# Misaka-v1_0.net
KiCad netlist of a schematic drawn in Altium Designer
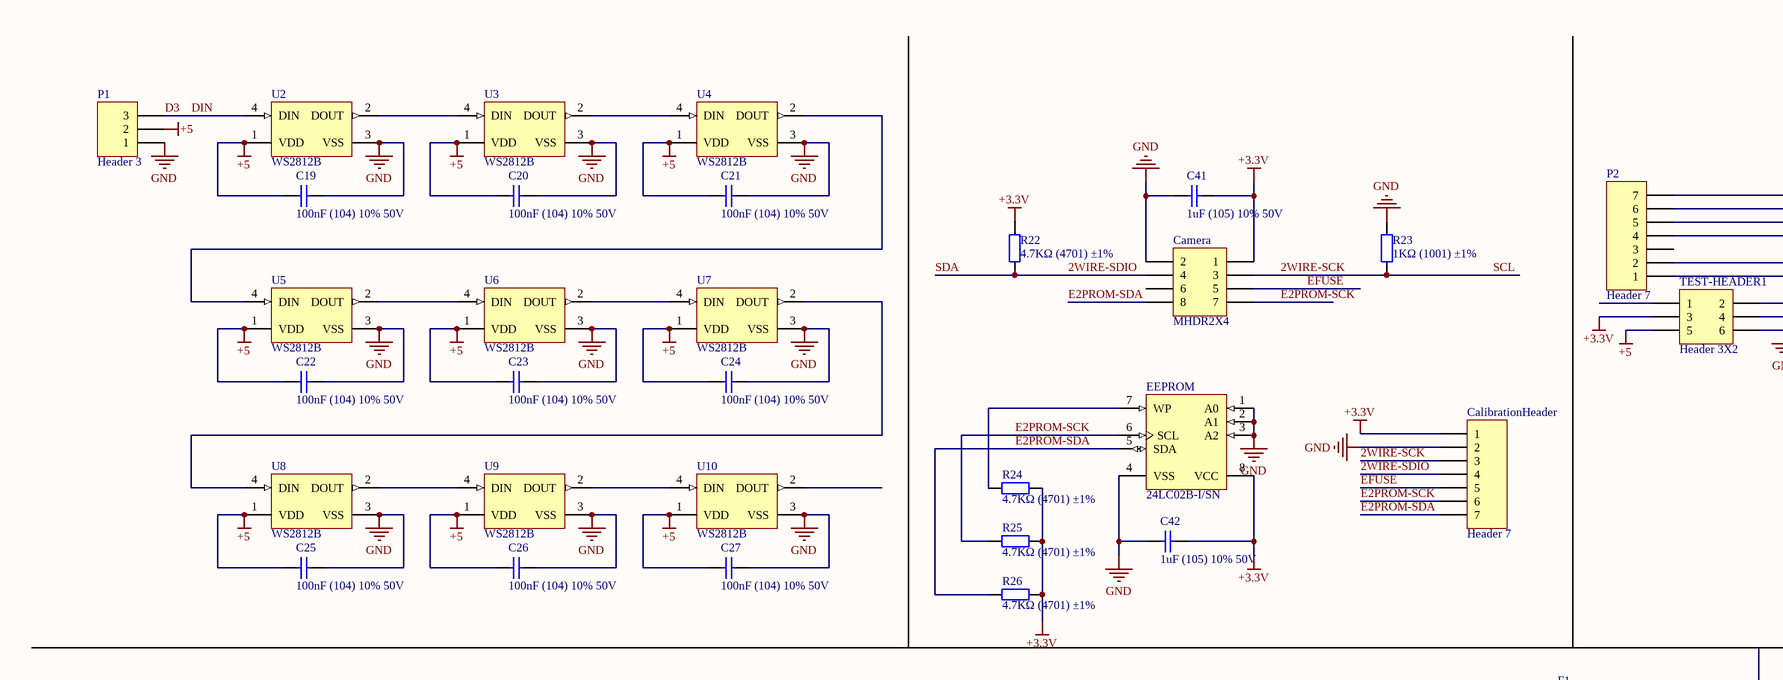
[diagram p0: Misaka-v1.0.SchDoc, top left]
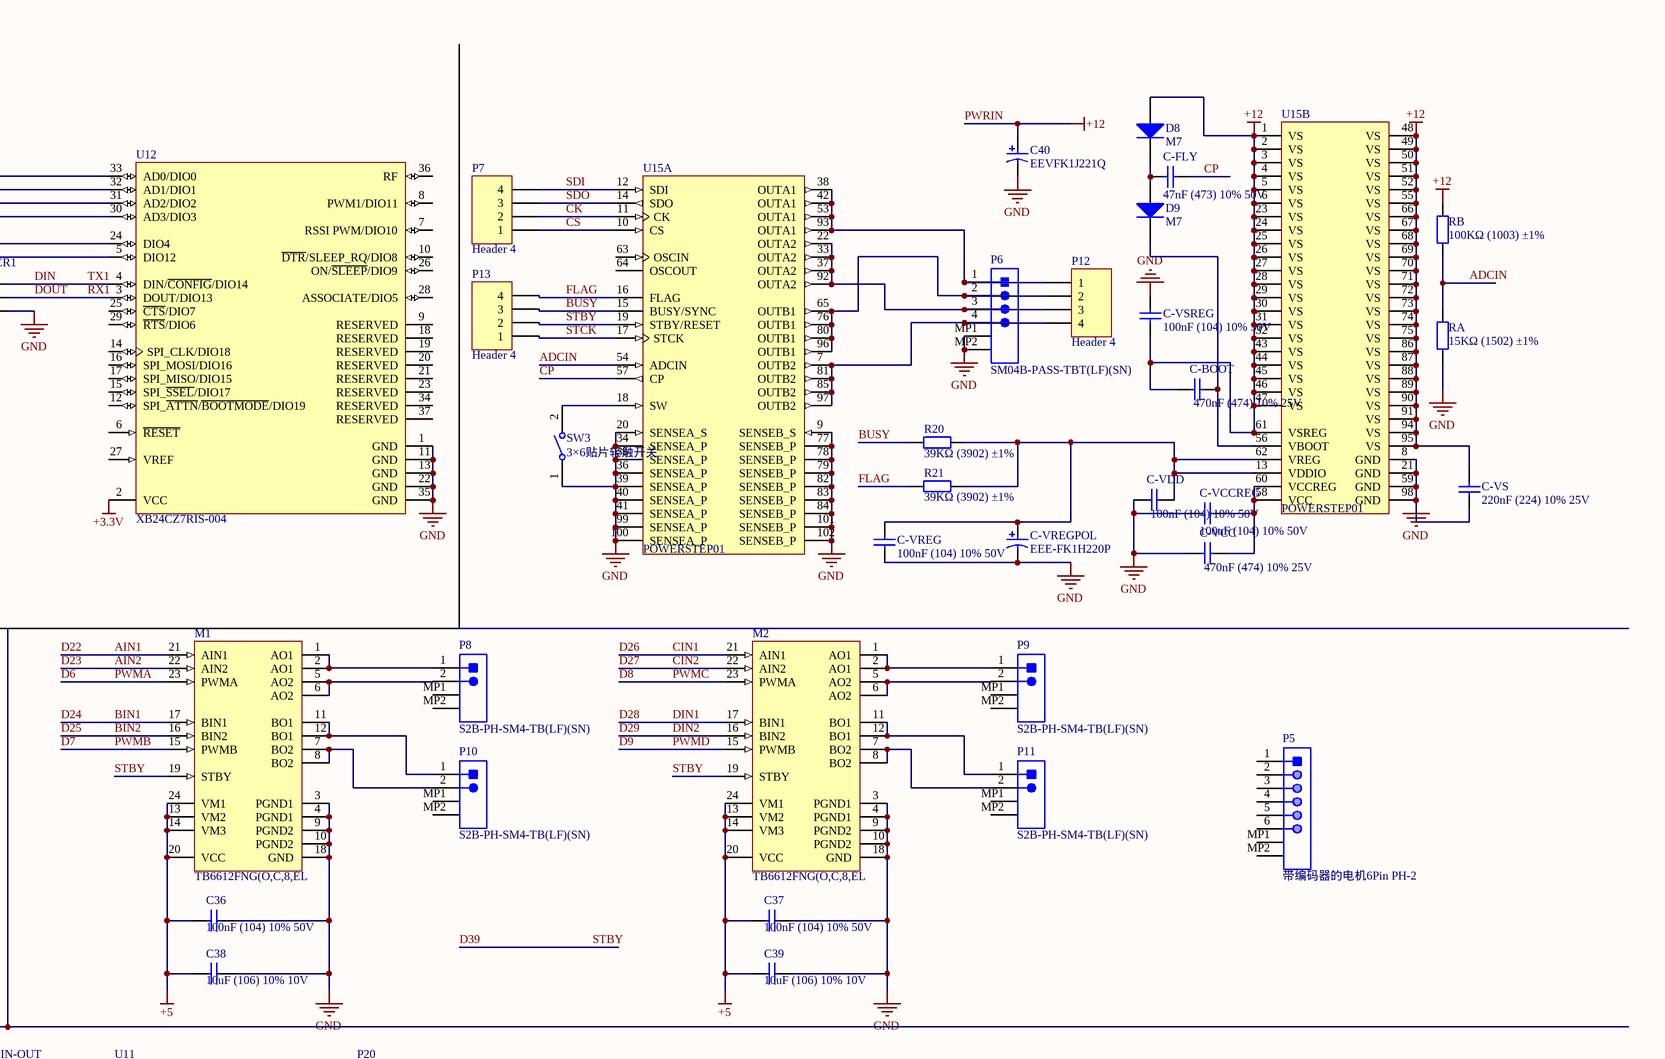
[diagram p1: Misaka-v1.0.SchDoc, top right]
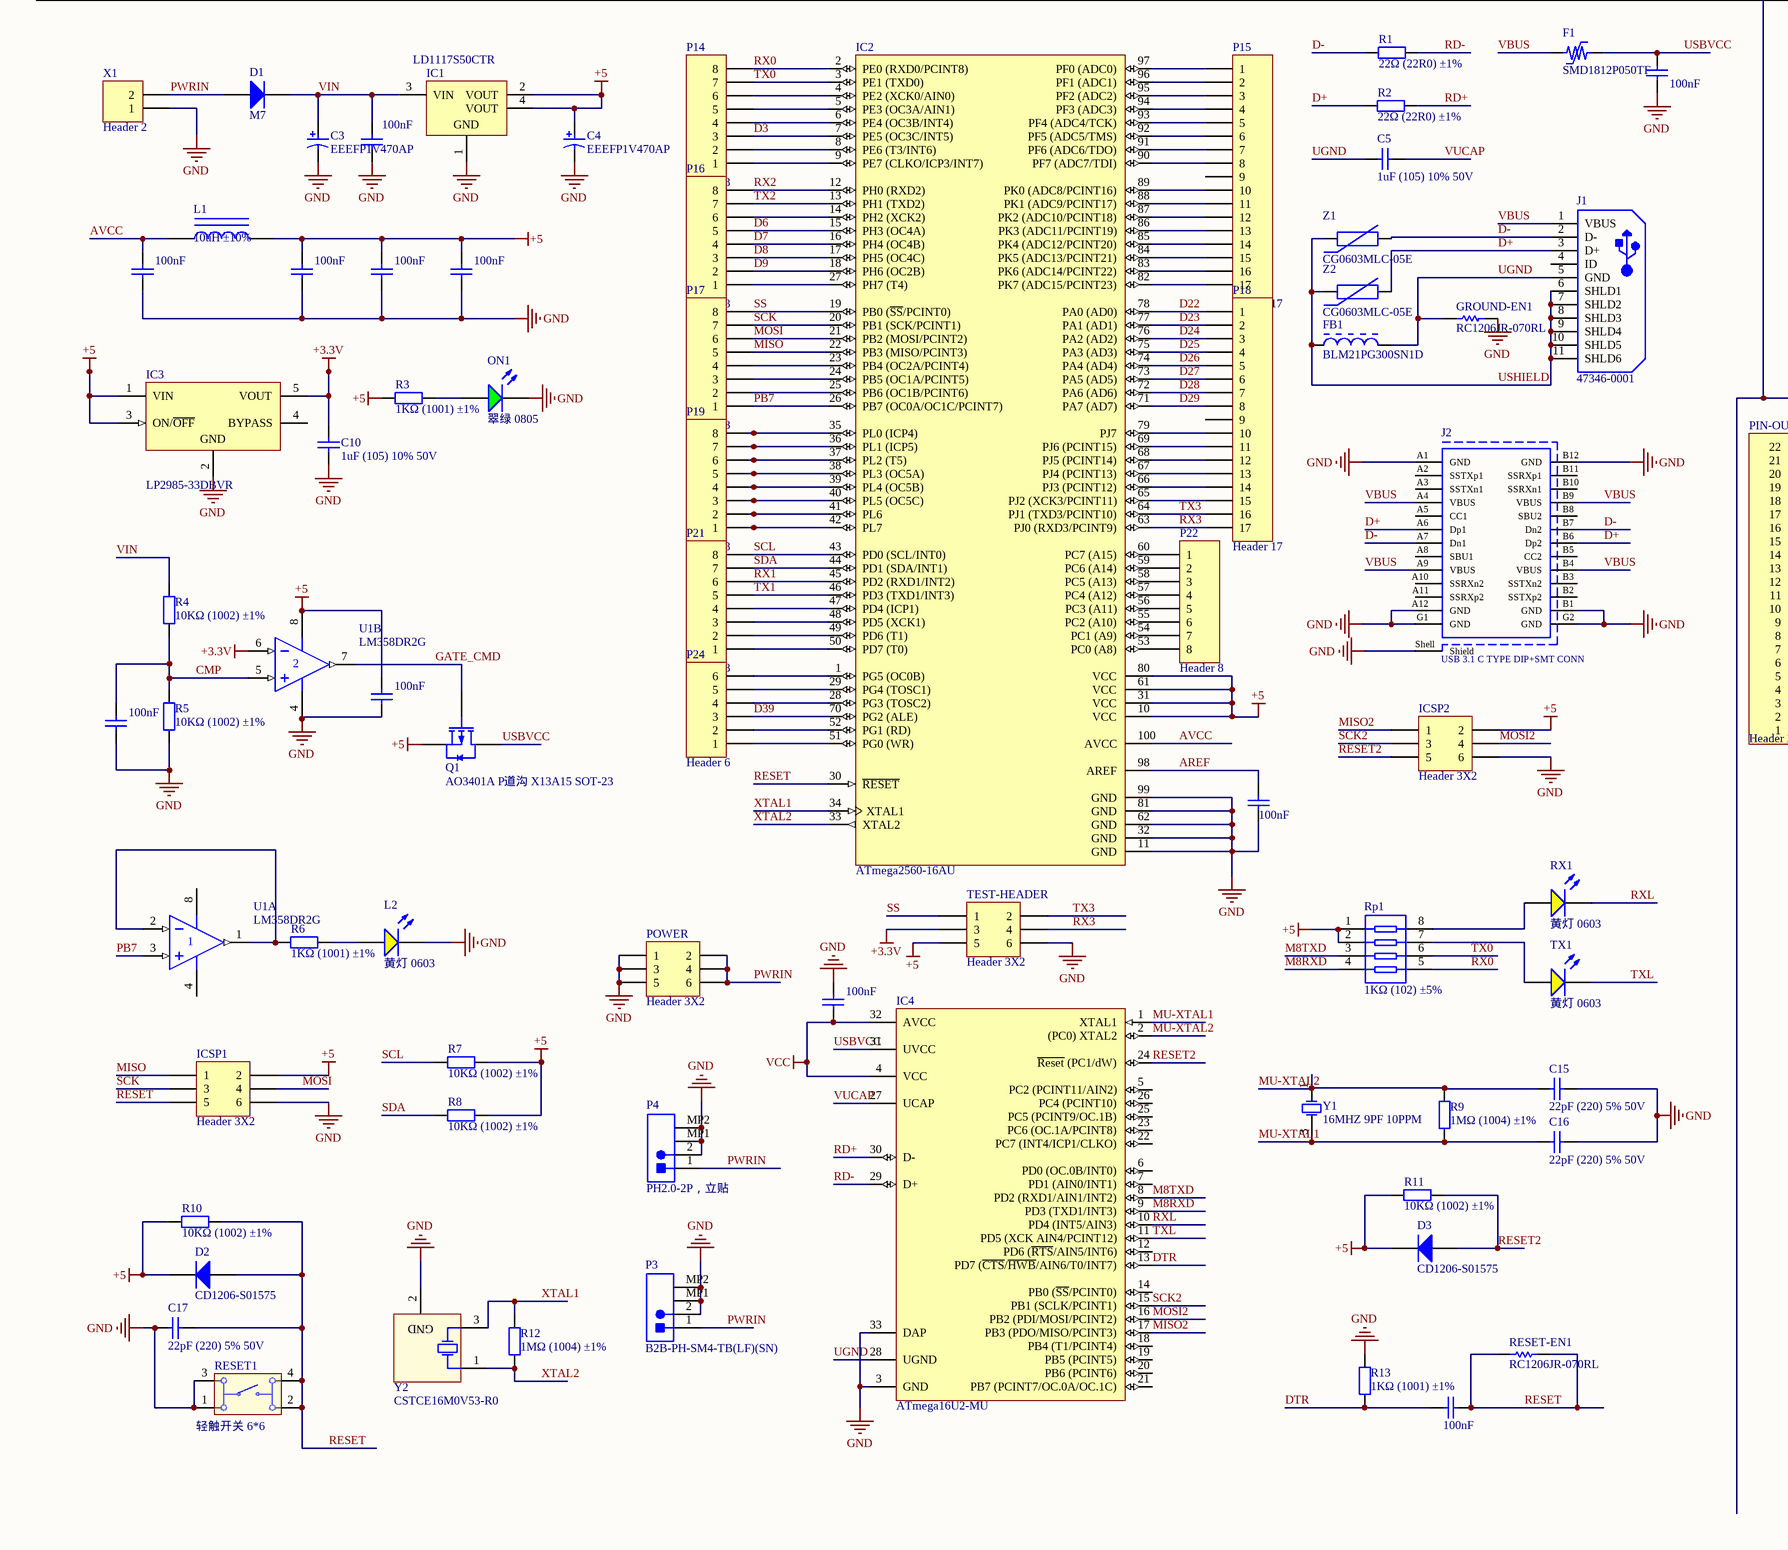
[diagram p2: Misaka-v1.0.SchDoc, bottom left]
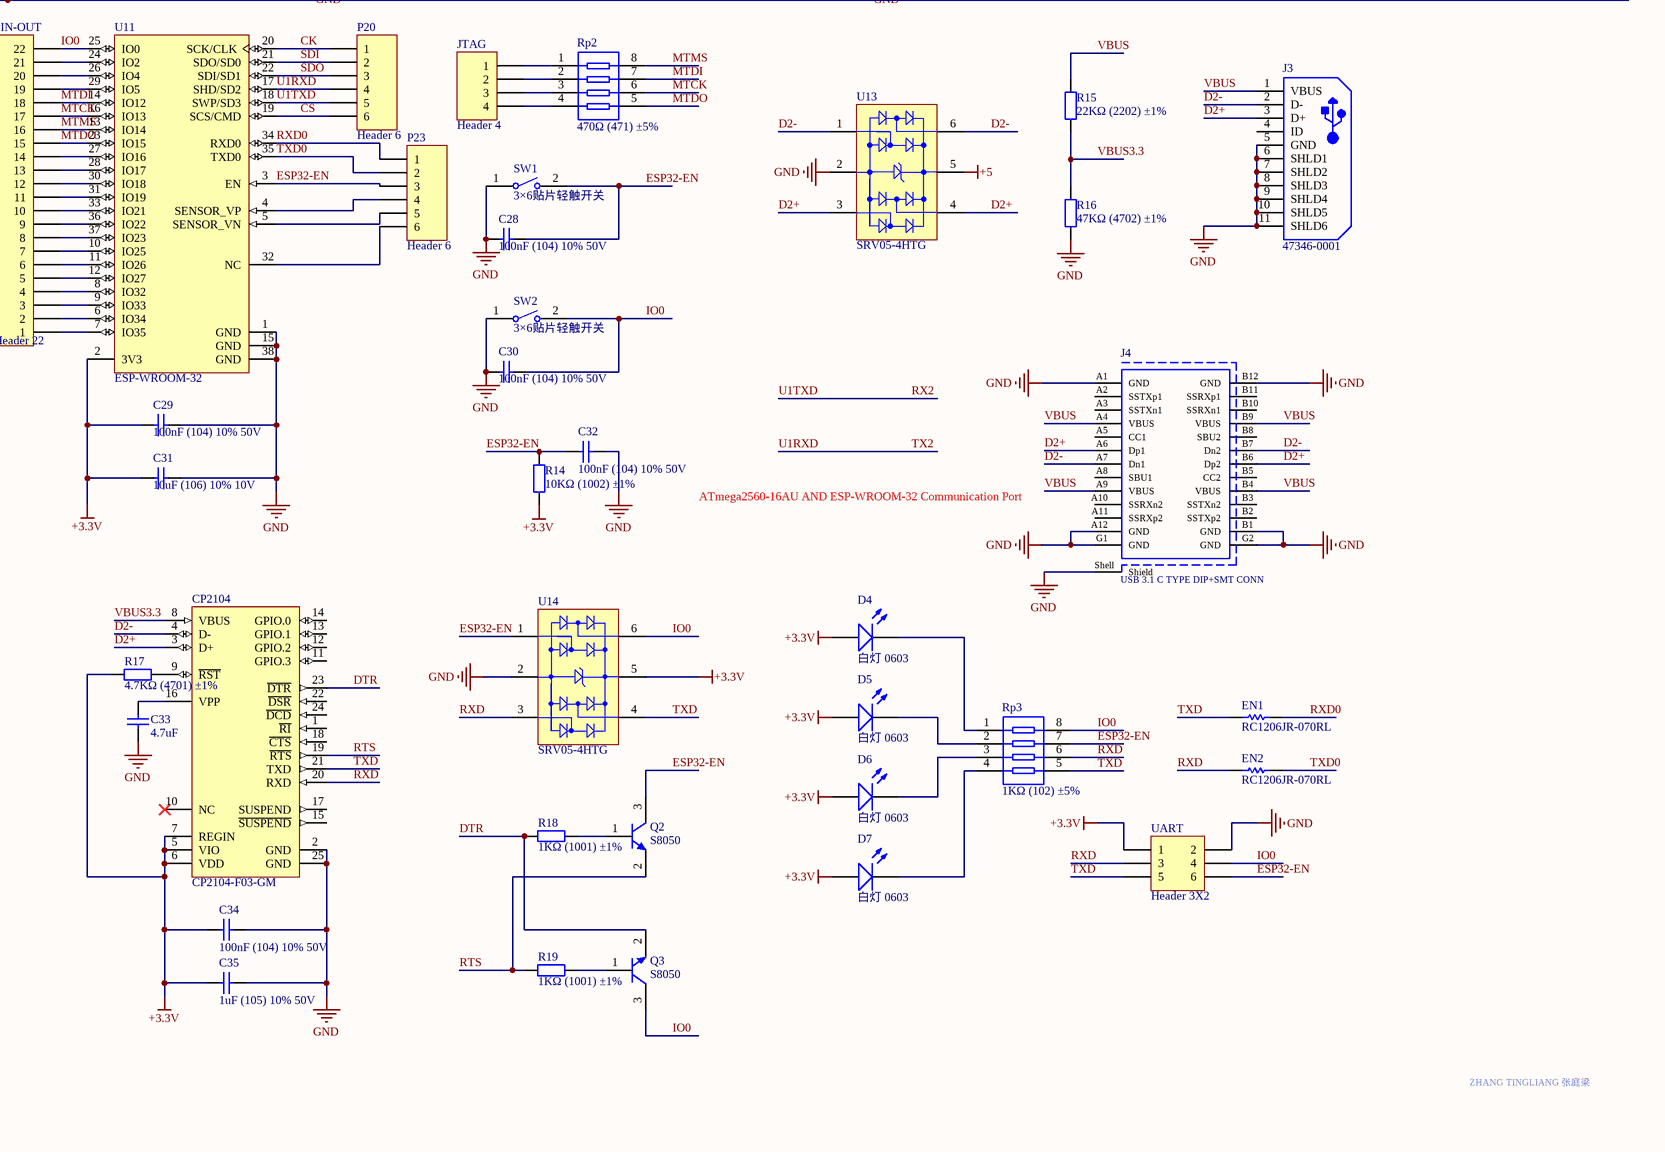
[diagram p3: Misaka-v1.0.SchDoc, bottom right]

(export (version "E")
  (design (tool "Eeschema 10.0.6"))
  (components
    (comp (ref "C-BOOT")
      (value "470nF (474) 10% 25V")
      (footprint "0603_C")
      (description "贴片电容")
      (libsource (lib "Miscellaneous Devices LC") (part "0603 470nF (474) 10% 25V"))
    )
    (comp (ref "C-FLY")
      (value "47nF (473) 10% 50V")
      (footprint "0603_C")
      (description "贴片电容")
      (libsource (lib "Miscellaneous Devices LC") (part "0603 47nF (473) 10% 50V"))
    )
    (comp (ref "C-VCC")
      (value "470nF (474) 10% 25V")
      (footprint "0603_C")
      (description "贴片电容")
      (libsource (lib "Miscellaneous Devices LC") (part "0603 470nF (474) 10% 25V"))
    )
    (comp (ref "C-VCCREG")
      (value "100nF (104) 10% 50V")
      (footprint "0603_C")
      (description "贴片电容")
      (libsource (lib "Miscellaneous Devices LC") (part "0603 100nF (104) 10% 50V"))
    )
    (comp (ref "C-VDD")
      (value "100nF (104) 10% 50V")
      (footprint "0603_C")
      (description "贴片电容")
      (libsource (lib "Miscellaneous Devices LC") (part "0603 100nF (104) 10% 50V"))
    )
    (comp (ref "C-VREG")
      (value "100nF (104) 10% 50V")
      (footprint "0603_C")
      (description "贴片电容")
      (libsource (lib "Miscellaneous Devices LC") (part "0603 100nF (104) 10% 50V"))
    )
    (comp (ref "C-VREGPOL")
      (value "EEE-FK1H220P")
      (footprint "PNSC-EEE-FK1H220P_L")
      (description "Cap Aluminum Lytic, 22 uF, +/- 20%, 6.3 to 100 V, -55 to 105 degC, 2-Pin SMD, RoHS, Tape and Reel")
      (fields (field (name "MANUFACTURER") "Panasonic"))
      (libsource (lib "Altium Content Vault") (part "CAP-P-2"))
    )
    (comp (ref "C-VS")
      (value "220nF (224) 10% 25V")
      (footprint "0603_C")
      (description "贴片电容")
      (libsource (lib "Miscellaneous Devices LC") (part "0603 220nF (224) 10% 25V"))
    )
    (comp (ref "C-VSREG")
      (value "100nF (104) 10% 50V")
      (footprint "0603_C")
      (description "贴片电容")
      (libsource (lib "Miscellaneous Devices LC") (part "0603 100nF (104) 10% 50V"))
    )
    (comp (ref "C1")
      (value "100nF")
      (footprint "0603_C")
      (description "贴片电容")
      (libsource (lib "Miscellaneous Devices LC") (part "0603 100nF (104) 10% 50V"))
    )
    (comp (ref "C2")
      (value "100nF")
      (footprint "0603_C")
      (description "贴片电容")
      (libsource (lib "Miscellaneous Devices LC") (part "0603 100nF (104) 10% 50V"))
    )
    (comp (ref "C3")
      (value "EEEFP1V470AP")
      (footprint "PNSC-FP-V-D_V")
      (fields (field (name "MANUFACTURER") "Panasonic"))
      (libsource (lib "Altium Content Vault") (part "CAP-P-2"))
    )
    (comp (ref "C4")
      (value "EEEFP1V470AP")
      (footprint "PNSC-FP-V-D_V")
      (fields (field (name "MANUFACTURER") "Panasonic"))
      (libsource (lib "Altium Content Vault") (part "CAP-P-2"))
    )
    (comp (ref "C5")
      (value "1uF (105) 10% 50V")
      (footprint "0603_C")
      (description "贴片电容")
      (libsource (lib "Miscellaneous Devices LC") (part "0603 1uF (105) 10% 50V"))
    )
    (comp (ref "C6")
      (value "100nF")
      (footprint "0603_C")
      (description "贴片电容")
      (libsource (lib "Miscellaneous Devices LC") (part "0603 100nF (104) 10% 50V"))
    )
    (comp (ref "C7")
      (value "100nF")
      (footprint "0603_C")
      (description "贴片电容")
      (libsource (lib "Miscellaneous Devices LC") (part "0603 100nF (104) 10% 50V"))
    )
    (comp (ref "C8")
      (value "100nF")
      (footprint "0603_C")
      (description "贴片电容")
      (libsource (lib "Miscellaneous Devices LC") (part "0603 100nF (104) 10% 50V"))
    )
    (comp (ref "C9")
      (value "100nF")
      (footprint "0603_C")
      (description "贴片电容")
      (libsource (lib "Miscellaneous Devices LC") (part "0603 100nF (104) 10% 50V"))
    )
    (comp (ref "C10")
      (value "1uF (105) 10% 50V")
      (footprint "0603_C")
      (description "贴片电容")
      (libsource (lib "Miscellaneous Devices LC") (part "0603 1uF (105) 10% 50V"))
    )
    (comp (ref "C11")
      (value "100nF")
      (footprint "0603_C")
      (description "贴片电容")
      (libsource (lib "Miscellaneous Devices LC") (part "0603 100nF (104) 10% 50V"))
    )
    (comp (ref "C12")
      (value "100nF")
      (footprint "0603_C")
      (description "贴片电容")
      (libsource (lib "Miscellaneous Devices LC") (part "0603 100nF (104) 10% 50V"))
    )
    (comp (ref "C13")
      (value "100nF")
      (footprint "0603_C")
      (description "贴片电容")
      (libsource (lib "Miscellaneous Devices LC") (part "0603 100nF (104) 10% 50V"))
    )
    (comp (ref "C14")
      (value "100nF")
      (footprint "0603_C")
      (description "贴片电容")
      (libsource (lib "Miscellaneous Devices LC") (part "0603 100nF (104) 10% 50V"))
    )
    (comp (ref "C15")
      (value "22pF (220) 5% 50V")
      (footprint "0603_C")
      (description "贴片电容")
      (libsource (lib "Miscellaneous Devices LC") (part "0603 22pF (220) 5% 50V"))
    )
    (comp (ref "C16")
      (value "22pF (220) 5% 50V")
      (footprint "0603_C")
      (description "贴片电容")
      (libsource (lib "Miscellaneous Devices LC") (part "0603 22pF (220) 5% 50V"))
    )
    (comp (ref "C17")
      (value "22pF (220) 5% 50V")
      (footprint "0603_C")
      (description "贴片电容")
      (libsource (lib "Miscellaneous Devices LC") (part "0603 22pF (220) 5% 50V"))
    )
    (comp (ref "C18")
      (value "100nF")
      (footprint "0603_C")
      (description "贴片电容")
      (libsource (lib "Miscellaneous Devices LC") (part "0603 100nF (104) 10% 50V"))
    )
    (comp (ref "C19")
      (value "100nF (104) 10% 50V")
      (footprint "0603_C")
      (description "贴片电容")
      (libsource (lib "Miscellaneous Devices LC") (part "0603 100nF (104) 10% 50V"))
    )
    (comp (ref "C20")
      (value "100nF (104) 10% 50V")
      (footprint "0603_C")
      (description "贴片电容")
      (libsource (lib "Miscellaneous Devices LC") (part "0603 100nF (104) 10% 50V"))
    )
    (comp (ref "C21")
      (value "100nF (104) 10% 50V")
      (footprint "0603_C")
      (description "贴片电容")
      (libsource (lib "Miscellaneous Devices LC") (part "0603 100nF (104) 10% 50V"))
    )
    (comp (ref "C22")
      (value "100nF (104) 10% 50V")
      (footprint "0603_C")
      (description "贴片电容")
      (libsource (lib "Miscellaneous Devices LC") (part "0603 100nF (104) 10% 50V"))
    )
    (comp (ref "C23")
      (value "100nF (104) 10% 50V")
      (footprint "0603_C")
      (description "贴片电容")
      (libsource (lib "Miscellaneous Devices LC") (part "0603 100nF (104) 10% 50V"))
    )
    (comp (ref "C24")
      (value "100nF (104) 10% 50V")
      (footprint "0603_C")
      (description "贴片电容")
      (libsource (lib "Miscellaneous Devices LC") (part "0603 100nF (104) 10% 50V"))
    )
    (comp (ref "C25")
      (value "100nF (104) 10% 50V")
      (footprint "0603_C")
      (description "贴片电容")
      (libsource (lib "Miscellaneous Devices LC") (part "0603 100nF (104) 10% 50V"))
    )
    (comp (ref "C26")
      (value "100nF (104) 10% 50V")
      (footprint "0603_C")
      (description "贴片电容")
      (libsource (lib "Miscellaneous Devices LC") (part "0603 100nF (104) 10% 50V"))
    )
    (comp (ref "C27")
      (value "100nF (104) 10% 50V")
      (footprint "0603_C")
      (description "贴片电容")
      (libsource (lib "Miscellaneous Devices LC") (part "0603 100nF (104) 10% 50V"))
    )
    (comp (ref "C28")
      (value "100nF (104) 10% 50V")
      (footprint "0603_C")
      (description "贴片电容")
      (libsource (lib "Miscellaneous Devices LC") (part "0603 100nF (104) 10% 50V"))
    )
    (comp (ref "C29")
      (value "100nF (104) 10% 50V")
      (footprint "0603_C")
      (description "贴片电容")
      (libsource (lib "Miscellaneous Devices LC") (part "0603 100nF (104) 10% 50V"))
    )
    (comp (ref "C30")
      (value "100nF (104) 10% 50V")
      (footprint "0603_C")
      (description "贴片电容")
      (libsource (lib "Miscellaneous Devices LC") (part "0603 100nF (104) 10% 50V"))
    )
    (comp (ref "C31")
      (value "10uF (106) 10% 10V")
      (footprint "0603_C")
      (description "贴片电容")
      (libsource (lib "Miscellaneous Devices LC") (part "0603 10uF (106) 10% 10V"))
    )
    (comp (ref "C32")
      (value "100nF (104) 10% 50V")
      (footprint "0603_C")
      (description "贴片电容")
      (libsource (lib "Miscellaneous Devices LC") (part "0603 100nF (104) 10% 50V"))
    )
    (comp (ref "C33")
      (value "4.7uF")
      (footprint "0603_C")
      (description "贴片电容")
      (libsource (lib "Miscellaneous Devices LC") (part "0603 4.7uF (475) 10% 16V"))
    )
    (comp (ref "C34")
      (value "100nF (104) 10% 50V")
      (footprint "0603_C")
      (description "贴片电容")
      (libsource (lib "Miscellaneous Devices LC") (part "0603 100nF (104) 10% 50V"))
    )
    (comp (ref "C35")
      (value "1uF (105) 10% 50V")
      (footprint "0603_C")
      (description "贴片电容")
      (libsource (lib "Miscellaneous Devices LC") (part "0603 1uF (105) 10% 50V"))
    )
    (comp (ref "C36")
      (value "100nF (104) 10% 50V")
      (footprint "0603_C")
      (description "贴片电容")
      (libsource (lib "Miscellaneous Devices LC") (part "0603 100nF (104) 10% 50V"))
    )
    (comp (ref "C37")
      (value "100nF (104) 10% 50V")
      (footprint "0603_C")
      (description "贴片电容")
      (libsource (lib "Miscellaneous Devices LC") (part "0603 100nF (104) 10% 50V"))
    )
    (comp (ref "C38")
      (value "10uF (106) 10% 10V")
      (footprint "0603_C")
      (description "贴片电容")
      (libsource (lib "Miscellaneous Devices LC") (part "0603 10uF (106) 10% 10V"))
    )
    (comp (ref "C39")
      (value "10uF (106) 10% 10V")
      (footprint "0603_C")
      (description "贴片电容")
      (libsource (lib "Miscellaneous Devices LC") (part "0603 10uF (106) 10% 10V"))
    )
    (comp (ref "C40")
      (value "EEVFK1J221Q")
      (footprint "PNSC-FK-V-H13_V")
      (fields (field (name "MANUFACTURER") "Panasonic"))
      (libsource (lib "Altium Content Vault") (part "CAP-P-2"))
    )
    (comp (ref "C41")
      (value "1uF (105) 10% 50V")
      (footprint "0603_C")
      (description "贴片电容")
      (libsource (lib "Miscellaneous Devices LC") (part "0603 1uF (105) 10% 50V"))
    )
    (comp (ref "C42")
      (value "1uF (105) 10% 50V")
      (footprint "0603_C")
      (description "贴片电容")
      (libsource (lib "Miscellaneous Devices LC") (part "0603 1uF (105) 10% 50V"))
    )
    (comp (ref "CalibrationHeader")
      (value "Header 7")
      (footprint "HDR1X7")
      (description "Header, 7-Pin")
      (fields (field (name "PUBLISHER") "Altium Limited"))
      (libsource (lib "Miscellaneous Connectors") (part "Header 7"))
    )
    (comp (ref "Camera")
      (value "MHDR2X4")
      (footprint "MHDR2X4")
      (description "Header, 4-Pin, Dual row")
      (fields (field (name "PUBLISHER") "Altium Limited"))
      (libsource (lib "Miscellaneous Connectors") (part "MHDR2X4"))
    )
    (comp (ref "CP2104")
      (value "CP2104-F03-GM")
      (footprint "SLAB-QFN-24-2675x2675TP_M")
      (fields (field (name "MANUFACTURER") "Silicon Labs"))
      (libsource (lib "Altium Content Vault") (part "SLAB-CP2104-QFN-24-25"))
    )
    (comp (ref "D1")
      (value "M7")
      (footprint "SMA(DO-214AC)_S1")
      (description "二极管")
      (libsource (lib "Miscellaneous Devices LC") (part "SMA(DO-214AC) M7"))
    )
    (comp (ref "D2")
      (value "CD1206-S01575")
      (footprint "BOUR-CD1206-S01575-2_L")
      (description "75 V Small Signal Switching Diode, 150 mA, 2.5 uA, 1026 Molded Package, RoHS, Tape and Reel")
      (fields (field (name "MANUFACTURER") "Bourns"))
      (libsource (lib "Altium Content Vault") (part "BOUR-A1K2-2"))
    )
    (comp (ref "D3")
      (value "CD1206-S01575")
      (footprint "BOUR-CD1206-S01575-2_L")
      (description "75 V Small Signal Switching Diode, 150 mA, 2.5 uA, 1026 Molded Package, RoHS, Tape and Reel")
      (fields (field (name "MANUFACTURER") "Bourns"))
      (libsource (lib "Altium Content Vault") (part "BOUR-A1K2-2"))
    )
    (comp (ref "D4")
      (value "白灯 0603")
      (footprint "0603_LED_S1")
      (description "发光二极管")
      (libsource (lib "Miscellaneous Devices LC") (part "0603 白灯"))
    )
    (comp (ref "D5")
      (value "白灯 0603")
      (footprint "0603_LED_S1")
      (description "发光二极管")
      (libsource (lib "Miscellaneous Devices LC") (part "0603 白灯"))
    )
    (comp (ref "D6")
      (value "白灯 0603")
      (footprint "0603_LED_S1")
      (description "发光二极管")
      (libsource (lib "Miscellaneous Devices LC") (part "0603 白灯"))
    )
    (comp (ref "D7")
      (value "白灯 0603")
      (footprint "0603_LED_S1")
      (description "发光二极管")
      (libsource (lib "Miscellaneous Devices LC") (part "0603 白灯"))
    )
    (comp (ref "D8")
      (value "M7")
      (footprint "SMA(DO-214AC)_S1")
      (description "二极管")
      (libsource (lib "Miscellaneous Devices LC") (part "SMA(DO-214AC) M7"))
    )
    (comp (ref "D9")
      (value "M7")
      (footprint "SMA(DO-214AC)_S1")
      (description "二极管")
      (libsource (lib "Miscellaneous Devices LC") (part "SMA(DO-214AC) M7"))
    )
    (comp (ref "EEPROM")
      (value "24LC02B-I/SN")
      (footprint "SOIC-SN8_N")
      (description "2Kbit, 400kHz, 2.5V, I2C Serial EEPROM, 8-Pin SOIC 150mil, Industrial Temperature")
      (libsource (lib "Altium Content Vault") (part "MEM-SEEPROM-34AA02-IL8"))
    )
    (comp (ref "EN1")
      (value "RC1206JR-070RL")
      (footprint "RESC3116X65X40ML10T20")
      (description "Chip Resistor, 0 Ohm, +/- 5%, -55 to 155 degC, 1206 (3216 Metric), RoHS, Tape and Reel")
      (fields (field (name "MANUFACTURER") "Yageo") (field (name "TOLERANCE") "5%"))
      (libsource (lib "Altium Content Vault") (part "RES-2"))
    )
    (comp (ref "EN2")
      (value "RC1206JR-070RL")
      (footprint "RESC3116X65X40ML10T20")
      (description "Chip Resistor, 0 Ohm, +/- 5%, -55 to 155 degC, 1206 (3216 Metric), RoHS, Tape and Reel")
      (fields (field (name "MANUFACTURER") "Yageo") (field (name "TOLERANCE") "5%"))
      (libsource (lib "Altium Content Vault") (part "RES-2"))
    )
    (comp (ref "F1")
      (value "SMD1812P050TF")
      (footprint "BOUR-MF-MSMF050-2_V")
      (description "PTC Resettable Fuse, 15 V, 500 mA, -40 to 85 degC, 2-Pin SMD, RoHS, Tape and Reel")
      (fields (field (name "MANUFACTURER") "Bourns"))
      (libsource (lib "Altium Content Vault") (part "PPTC-2"))
    )
    (comp (ref "FB1")
      (value "BLM21PG300SN1D")
      (footprint "MURA-BLM21-B40-CHIP-2_V2")
      (fields (field (name "MANUFACTURER") "Murata"))
      (libsource (lib "Altium Content Vault") (part "MURA-FB-2"))
    )
    (comp (ref "GROUND-EN1")
      (value "RC1206JR-070RL")
      (footprint "RESC3116X65X40ML10T20")
      (description "Chip Resistor, 0 Ohm, +/- 5%, -55 to 155 degC, 1206 (3216 Metric), RoHS, Tape and Reel")
      (fields (field (name "MANUFACTURER") "Yageo") (field (name "TOLERANCE") "5%"))
      (libsource (lib "Altium Content Vault") (part "RES-2"))
    )
    (comp (ref "IC1")
      (value "LD1117S50CTR")
      (footprint "SOT-223_N")
      (libsource (lib "Altium Content Vault") (part "PM-REG-LD1117-SOT4"))
    )
    (comp (ref "IC2")
      (value "ATmega2560-16AU")
      (footprint "100A_M")
      (libsource (lib "Altium Content Vault") (part "MC-8B-ATM640-SQ100"))
    )
    (comp (ref "IC3")
      (value "LP2985-33DBVR")
      (footprint "DBV0005A_M")
      (fields (field (name "MANUFACTURER") "Texas Instruments"))
      (libsource (lib "Altium Content Vault") (part "TI-LP2985_A-10DBV5"))
    )
    (comp (ref "IC4")
      (value "ATmega16U2-MU")
      (footprint "32PG_N")
      (libsource (lib "Altium Content Vault") (part "MC-8B-ATM8U2-SQ33"))
    )
    (comp (ref "ICSP1")
      (value "Header 3X2")
      (footprint "HDR2X3")
      (description "Header, 3-Pin, Dual row")
      (fields (field (name "PUBLISHER") "Altium Limited"))
      (libsource (lib "Miscellaneous Connectors") (part "Header 3X2"))
    )
    (comp (ref "ICSP2")
      (value "Header 3X2")
      (footprint "HDR2X3")
      (description "Header, 3-Pin, Dual row")
      (fields (field (name "PUBLISHER") "Altium Limited"))
      (libsource (lib "Miscellaneous Connectors") (part "Header 3X2"))
    )
    (comp (ref "J1")
      (value "47346-0001")
      (footprint "MOLX-47346-0001-5_V")
      (description "Micro-USB B Receptacle with Flange, -30 to 85 degC, 5-Pin SMD, RoHS, Tape and Reel")
      (fields (field (name "MANUFACTURER") "Molex"))
      (libsource (lib "Altium Content Vault") (part "MOLX-47346-0001-5"))
    )
    (comp (ref "J2")
      (value "USB 3.1 C TYPE DIP+SMT CONN")
      (footprint "632723100011")
      (description "USB 3.1 Type C Receptacle WR-COM, Horizontal, SMT / THT")
      (fields
        (field (name "PART NUMBER") "632723100011")
        (field (name "MANUFACTURER") "Wurth Elektronik")
        (field (name "PUBLISHER") "WurthElektronik")
      )
      (libsource (lib "Altium Content Vault") (part "WE-632723X00011"))
    )
    (comp (ref "J3")
      (value "47346-0001")
      (footprint "MOLX-47346-0001-5_V")
      (description "Micro-USB B Receptacle with Flange, -30 to 85 degC, 5-Pin SMD, RoHS, Tape and Reel")
      (fields (field (name "MANUFACTURER") "Molex"))
      (libsource (lib "Altium Content Vault") (part "MOLX-47346-0001-5"))
    )
    (comp (ref "J4")
      (value "USB 3.1 C TYPE DIP+SMT CONN")
      (footprint "632723100011")
      (description "USB 3.1 Type C Receptacle WR-COM, Horizontal, SMT / THT")
      (fields
        (field (name "PART NUMBER") "632723100011")
        (field (name "MANUFACTURER") "Wurth Elektronik")
        (field (name "PUBLISHER") "WurthElektronik")
      )
      (libsource (lib "Altium Content Vault") (part "WE-632723X00011"))
    )
    (comp (ref "JTAG")
      (value "Header 4")
      (footprint "HDR1X4")
      (description "Header, 4-Pin")
      (fields (field (name "PUBLISHER") "Altium Limited"))
      (libsource (lib "") (part "Header 4_1"))
    )
    (comp (ref "L1")
      (value "10uH ±10%")
      (footprint "0603_L")
      (description "贴片电感")
      (libsource (lib "Miscellaneous Devices LC") (part "0603 10uH 10%"))
    )
    (comp (ref "L2")
      (value "黄灯 0603")
      (footprint "0603_LED_S1")
      (description "发光二极管")
      (libsource (lib "Miscellaneous Devices LC") (part "0603 黄灯"))
    )
    (comp (ref "M1")
      (value "TB6612FNG(O,C,8,EL")
      (footprint "TOSH-SSOP24-P-300-0.65A_M")
      (fields (field (name "MANUFACTURER") "Toshiba"))
      (libsource (lib "Altium Content Vault") (part "TOSH-TB6612FNG-SSOP24"))
    )
    (comp (ref "M2")
      (value "TB6612FNG(O,C,8,EL")
      (footprint "TOSH-SSOP24-P-300-0.65A_M")
      (fields (field (name "MANUFACTURER") "Toshiba"))
      (libsource (lib "Altium Content Vault") (part "TOSH-TB6612FNG-SSOP24"))
    )
    (comp (ref "ON1")
      (value "翠绿 0805")
      (footprint "0805_LED_S1")
      (description "发光二极管")
      (libsource (lib "Miscellaneous Devices LC") (part "0805 翠绿"))
    )
    (comp (ref "P1")
      (value "Header 3")
      (footprint "HDR1X3")
      (description "Header, 3-Pin")
      (fields (field (name "PUBLISHER") "Altium Limited"))
      (libsource (lib "Miscellaneous Connectors") (part "Header 3"))
    )
    (comp (ref "P2")
      (value "Header 7")
      (footprint "HDR1X7")
      (description "Header, 7-Pin")
      (fields (field (name "PUBLISHER") "Altium Limited"))
      (libsource (lib "") (part "Header 7_1"))
    )
    (comp (ref "P3")
      (value "B2B-PH-SM4-TB(LF)(SN)")
      (footprint "JST-B2B-PH-SM4-TB-2_V")
      (description "Male Header, Pitch 2 mm, 1 x 2 Position, Height 6.6 mm, RoHS, Tape and Reel")
      (fields (field (name "MANUFACTURER") "JST"))
      (libsource (lib "") (part "CN-1P-2M-R2_1"))
    )
    (comp (ref "P4")
      (value "PH2.0-2P，立贴")
      (footprint "JST-B2B-PH-SM4-TB-2_V")
      (fields (field (name "MANUFACTURER") "JST"))
      (libsource (lib "") (part "CN-1P-2M-R2_1"))
    )
    (comp (ref "P5")
      (value "带编码器的电机6Pin PH-2")
      (footprint "JST-S6B-PH-SM4-TB(LF)(SN)_V")
      (description "Male Header, Pitch 2 mm, 1 x 6 Position, Height 5.5 mm, -25 to 85 degC\r\nS6B-PH-SM4-TB(LF)(SN)")
      (fields (field (name "MANUFACTURER") "JST"))
      (libsource (lib "Altium Content Vault") (part "CN-1P-2M-R6"))
    )
    (comp (ref "P6")
      (value "SM04B-PASS-TBT(LF)(SN)")
      (footprint "JST-SM04B-PASS-TBT(LF)(SN)_V")
      (description "Male Header, Pitch 2 mm, 1 x 4 Position, Height 5.7 mm, -25 to 85 degC, RoHS, Tape and Reel")
      (fields (field (name "MANUFACTURER") "Japan Solderless Terminals"))
      (libsource (lib "Altium Content Vault") (part "CN-1P-2M-R4_A"))
    )
    (comp (ref "P7")
      (value "Header 4")
      (footprint "HDR1X4")
      (description "Header, 4-Pin")
      (fields (field (name "PUBLISHER") "Altium Limited"))
      (libsource (lib "Miscellaneous Connectors") (part "Header 4"))
    )
    (comp (ref "P8")
      (value "S2B-PH-SM4-TB(LF)(SN)")
      (footprint "JST- S2B-PH-SM4-TB(LF)(SN)-2_V")
      (description "Male Header, Pitch 2 mm, 1 x 2 Position, Height 5.5 mm, -25 to 85 degC, RoHS, Tape and Reel")
      (libsource (lib "Altium Content Vault") (part "CN-1P-2M-R2"))
    )
    (comp (ref "P9")
      (value "S2B-PH-SM4-TB(LF)(SN)")
      (footprint "JST- S2B-PH-SM4-TB(LF)(SN)-2_V")
      (description "Male Header, Pitch 2 mm, 1 x 2 Position, Height 5.5 mm, -25 to 85 degC, RoHS, Tape and Reel")
      (libsource (lib "Altium Content Vault") (part "CN-1P-2M-R2"))
    )
    (comp (ref "P10")
      (value "S2B-PH-SM4-TB(LF)(SN)")
      (footprint "JST- S2B-PH-SM4-TB(LF)(SN)-2_V")
      (description "Male Header, Pitch 2 mm, 1 x 2 Position, Height 5.5 mm, -25 to 85 degC, RoHS, Tape and Reel")
      (libsource (lib "Altium Content Vault") (part "CN-1P-2M-R2"))
    )
    (comp (ref "P11")
      (value "S2B-PH-SM4-TB(LF)(SN)")
      (footprint "JST- S2B-PH-SM4-TB(LF)(SN)-2_V")
      (description "Male Header, Pitch 2 mm, 1 x 2 Position, Height 5.5 mm, -25 to 85 degC, RoHS, Tape and Reel")
      (libsource (lib "Altium Content Vault") (part "CN-1P-2M-R2"))
    )
    (comp (ref "P12")
      (value "Header 4")
      (footprint "HDR1X4")
      (description "Header, 4-Pin")
      (fields (field (name "PUBLISHER") "Altium Limited"))
      (libsource (lib "") (part "Header 4_2"))
    )
    (comp (ref "P13")
      (value "Header 4")
      (footprint "HDR1X4")
      (description "Header, 4-Pin")
      (fields (field (name "PUBLISHER") "Altium Limited"))
      (libsource (lib "Miscellaneous Connectors") (part "Header 4"))
    )
    (comp (ref "P14")
      (value "Header 8")
      (footprint "HDR1X8")
      (description "Header, 8-Pin")
      (fields (field (name "PUBLISHER") "Altium Limited"))
      (libsource (lib "Miscellaneous Connectors") (part "Header 8"))
    )
    (comp (ref "P15")
      (value "Header 17")
      (footprint "HDR1X17")
      (description "Header, 17-Pin")
      (fields (field (name "PUBLISHER") "Altium Limited"))
      (libsource (lib "Miscellaneous Connectors") (part "Header 17"))
    )
    (comp (ref "P16")
      (value "Header 8")
      (footprint "HDR1X8")
      (description "Header, 8-Pin")
      (fields (field (name "PUBLISHER") "Altium Limited"))
      (libsource (lib "Miscellaneous Connectors") (part "Header 8"))
    )
    (comp (ref "P17")
      (value "Header 8")
      (footprint "HDR1X8")
      (description "Header, 8-Pin")
      (fields (field (name "PUBLISHER") "Altium Limited"))
      (libsource (lib "Miscellaneous Connectors") (part "Header 8"))
    )
    (comp (ref "P18")
      (value "Header 17")
      (footprint "HDR1X17")
      (description "Header, 17-Pin")
      (fields (field (name "PUBLISHER") "Altium Limited"))
      (libsource (lib "Miscellaneous Connectors") (part "Header 17"))
    )
    (comp (ref "P19")
      (value "Header 8")
      (footprint "HDR1X8")
      (description "Header, 8-Pin")
      (fields (field (name "PUBLISHER") "Altium Limited"))
      (libsource (lib "Miscellaneous Connectors") (part "Header 8"))
    )
    (comp (ref "P20")
      (value "Header 6")
      (footprint "HDR1X6")
      (description "Header, 6-Pin")
      (fields (field (name "PUBLISHER") "Altium Limited"))
      (libsource (lib "Miscellaneous Connectors") (part "Header 6"))
    )
    (comp (ref "P21")
      (value "Header 8")
      (footprint "HDR1X8")
      (description "Header, 8-Pin")
      (fields (field (name "PUBLISHER") "Altium Limited"))
      (libsource (lib "Miscellaneous Connectors") (part "Header 8"))
    )
    (comp (ref "P22")
      (value "Header 8")
      (footprint "HDR1X8")
      (description "Header, 8-Pin")
      (fields (field (name "PUBLISHER") "Altium Limited"))
      (libsource (lib "") (part "Header 8_1"))
    )
    (comp (ref "P23")
      (value "Header 6")
      (footprint "HDR1X6")
      (description "Header, 6-Pin")
      (fields (field (name "PUBLISHER") "Altium Limited"))
      (libsource (lib "Miscellaneous Connectors") (part "Header 6"))
    )
    (comp (ref "P24")
      (value "Header 6")
      (footprint "HDR1X6")
      (description "Header, 6-Pin")
      (fields (field (name "PUBLISHER") "Altium Limited"))
      (libsource (lib "") (part "Header 6_1"))
    )
    (comp (ref "PIN-OUT")
      (value "Header 22")
      (footprint "HDR1X22")
      (description "Header, 22-Pin")
      (fields (field (name "PUBLISHER") "Altium Limited"))
      (libsource (lib "Miscellaneous Connectors") (part "Header 22"))
    )
    (comp (ref "POWER")
      (value "Header 3X2")
      (footprint "HDR2X3")
      (description "Header, 3-Pin, Dual row")
      (fields (field (name "PUBLISHER") "Altium Limited"))
      (libsource (lib "Miscellaneous Connectors") (part "Header 3X2"))
    )
    (comp (ref "Q1")
      (value "AO3401A P道沟 X13A15 SOT-23")
      (footprint "SOT-23-3L")
      (description "MOS(场效应管)")
      (libsource (lib "Miscellaneous Devices LC") (part "AO3401A P道沟 X13A15 SOT-23"))
    )
    (comp (ref "Q2")
      (value "S8050")
      (footprint "ONSC-SOT-23-3-318-08_V")
      (description "General Purpose Transistor, NPN Silicon, 3-Pin SOT-23, Pb-Free, Tape and Reel\r\nMMBT3904LT1G")
      (fields (field (name "MANUFACTURER") "On Semiconductor") (field (name "PARTNUMBER") "MMBT3904LT1G"))
      (libsource (lib "Altium Content Vault") (part "ONSC-NPN-B1E2C3-3"))
    )
    (comp (ref "Q3")
      (value "S8050")
      (footprint "ONSC-SOT-23-3-318-08_V")
      (description "General Purpose Transistor, NPN Silicon, 3-Pin SOT-23, Pb-Free, Tape and Reel\r\nMMBT3904LT1G")
      (fields (field (name "MANUFACTURER") "On Semiconductor") (field (name "PARTNUMBER") "MMBT3904LT1G"))
      (libsource (lib "Altium Content Vault") (part "ONSC-NPN-B1E2C3-3"))
    )
    (comp (ref "R1")
      (value "22Ω (22R0) ±1%")
      (footprint "0603_R")
      (description "贴片电阻")
      (libsource (lib "Miscellaneous Devices LC") (part "0603 22Ω (22R0) 1%"))
    )
    (comp (ref "R2")
      (value "22Ω (22R0) ±1%")
      (footprint "0603_R")
      (description "贴片电阻")
      (libsource (lib "Miscellaneous Devices LC") (part "0603 22Ω (22R0) 1%"))
    )
    (comp (ref "R3")
      (value "1KΩ (1001) ±1%")
      (footprint "0603_R")
      (description "贴片电阻")
      (libsource (lib "") (part "0603 1KΩ (1001) 1%_2"))
    )
    (comp (ref "R4")
      (value "10KΩ (1002) ±1%")
      (footprint "0603_R")
      (description "贴片电阻")
      (libsource (lib "Miscellaneous Devices LC") (part "0603 10KΩ (1002) 1%"))
    )
    (comp (ref "R5")
      (value "10KΩ (1002) ±1%")
      (footprint "0603_R")
      (description "贴片电阻")
      (libsource (lib "Miscellaneous Devices LC") (part "0603 10KΩ (1002) 1%"))
    )
    (comp (ref "R6")
      (value "1KΩ (1001) ±1%")
      (footprint "0603_R")
      (description "贴片电阻")
      (libsource (lib "") (part "0603 1KΩ (1001) 1%_2"))
    )
    (comp (ref "R7")
      (value "10KΩ (1002) ±1%")
      (footprint "0603_R")
      (description "贴片电阻")
      (libsource (lib "") (part "0603 10KΩ (1002) 1%_1"))
    )
    (comp (ref "R8")
      (value "10KΩ (1002) ±1%")
      (footprint "0603_R")
      (description "贴片电阻")
      (libsource (lib "") (part "0603 10KΩ (1002) 1%_1"))
    )
    (comp (ref "R9")
      (value "1MΩ (1004) ±1%")
      (footprint "0603_R")
      (description "贴片电阻")
      (libsource (lib "") (part "0603 1MΩ (1004) 1%_1"))
    )
    (comp (ref "R10")
      (value "10KΩ (1002) ±1%")
      (footprint "0603_R")
      (description "贴片电阻")
      (libsource (lib "") (part "0603 10KΩ (1002) 1%_1"))
    )
    (comp (ref "R11")
      (value "10KΩ (1002) ±1%")
      (footprint "0603_R")
      (description "贴片电阻")
      (libsource (lib "") (part "0603 10KΩ (1002) 1%_1"))
    )
    (comp (ref "R12")
      (value "1MΩ (1004) ±1%")
      (footprint "0603_R")
      (description "贴片电阻")
      (libsource (lib "Miscellaneous Devices LC") (part "0603 1MΩ (1004) 1%"))
    )
    (comp (ref "R13")
      (value "1KΩ (1001) ±1%")
      (footprint "0603_R")
      (description "贴片电阻")
      (libsource (lib "") (part "0603 1KΩ (1001) 1%_1"))
    )
    (comp (ref "R14")
      (value "10KΩ (1002) ±1%")
      (footprint "0603_R")
      (description "贴片电阻")
      (libsource (lib "Miscellaneous Devices LC") (part "0603 10KΩ (1002) 1%"))
    )
    (comp (ref "R15")
      (value "22KΩ (2202) ±1%")
      (footprint "0603_R")
      (description "贴片电阻")
      (libsource (lib "Miscellaneous Devices LC") (part "0603 22KΩ (2202) 1%"))
    )
    (comp (ref "R16")
      (value "47KΩ (4702) ±1%")
      (footprint "0603_R")
      (description "贴片电阻")
      (libsource (lib "Miscellaneous Devices LC") (part "0603 47KΩ (4702) 1%"))
    )
    (comp (ref "R17")
      (value "4.7KΩ (4701) ±1%")
      (footprint "0603_R")
      (description "贴片电阻")
      (libsource (lib "") (part "0603 4.7KΩ (4701) 1%_1"))
    )
    (comp (ref "R18")
      (value "1KΩ (1001) ±1%")
      (footprint "0603_R")
      (description "贴片电阻")
      (libsource (lib "") (part "0603 1KΩ (1001) 1%_2"))
    )
    (comp (ref "R19")
      (value "1KΩ (1001) ±1%")
      (footprint "0603_R")
      (description "贴片电阻")
      (libsource (lib "") (part "0603 1KΩ (1001) 1%_2"))
    )
    (comp (ref "R20")
      (value "39KΩ (3902) ±1%")
      (footprint "0603_R")
      (description "贴片电阻")
      (libsource (lib "Miscellaneous Devices LC") (part "0603 39KΩ (3902) 1%"))
    )
    (comp (ref "R21")
      (value "39KΩ (3902) ±1%")
      (footprint "0603_R")
      (description "贴片电阻")
      (libsource (lib "Miscellaneous Devices LC") (part "0603 39KΩ (3902) 1%"))
    )
    (comp (ref "R22")
      (value "4.7KΩ (4701) ±1%")
      (footprint "0603_R")
      (description "贴片电阻")
      (libsource (lib "Miscellaneous Devices LC") (part "0603 4.7KΩ (4701) 1%"))
    )
    (comp (ref "R23")
      (value "1KΩ (1001) ±1%")
      (footprint "0603_R")
      (description "贴片电阻")
      (libsource (lib "Miscellaneous Devices LC") (part "0603 1KΩ (1001) 1%"))
    )
    (comp (ref "R24")
      (value "4.7KΩ (4701) ±1%")
      (footprint "0603_R")
      (description "贴片电阻")
      (libsource (lib "") (part "0603 4.7KΩ (4701) 1%_2"))
    )
    (comp (ref "R25")
      (value "4.7KΩ (4701) ±1%")
      (footprint "0603_R")
      (description "贴片电阻")
      (libsource (lib "") (part "0603 4.7KΩ (4701) 1%_2"))
    )
    (comp (ref "R26")
      (value "4.7KΩ (4701) ±1%")
      (footprint "0603_R")
      (description "贴片电阻")
      (libsource (lib "") (part "0603 4.7KΩ (4701) 1%_2"))
    )
    (comp (ref "RA")
      (value "15KΩ (1502) ±1%")
      (footprint "0603_R")
      (description "贴片电阻")
      (libsource (lib "Miscellaneous Devices LC") (part "0603 15KΩ (1502) 1%"))
    )
    (comp (ref "RB")
      (value "100KΩ (1003) ±1%")
      (footprint "0603_R")
      (description "贴片电阻")
      (libsource (lib "Miscellaneous Devices LC") (part "0603 100KΩ (1003) 1%"))
    )
    (comp (ref "RESET-EN1")
      (value "RC1206JR-070RL")
      (footprint "RESC3116X65X40ML10T20")
      (description "Chip Resistor, 0 Ohm, +/- 5%, -55 to 155 degC, 1206 (3216 Metric), RoHS, Tape and Reel")
      (fields (field (name "MANUFACTURER") "Yageo") (field (name "TOLERANCE") "5%"))
      (libsource (lib "Altium Content Vault") (part "RES-2"))
    )
    (comp (ref "RESET1")
      (value "轻触开关 6*6")
      (footprint "430152043836")
      (description "WS-TASV SMD Tact Switch 6X6 mm")
      (fields (field (name "PARTNUMBER") "430152043836") (field (name "MANUFACTURER") "Wuerth Elektronik"))
      (libsource (lib "Altium Content Vault") (part "WE-TACT-SW-4"))
    )
    (comp (ref "Rp1")
      (value "1KΩ (102) ±5%")
      (footprint "0603_Rx4")
      (description "贴片排阻")
      (libsource (lib "Miscellaneous Devices LC") (part "0603*4  1KΩ (102) 5%"))
    )
    (comp (ref "Rp2")
      (value "470Ω (471) ±5%")
      (footprint "0603_Rx4")
      (description "贴片排阻")
      (libsource (lib "Miscellaneous Devices LC") (part "0603*4 470Ω (471) 5%"))
    )
    (comp (ref "Rp3")
      (value "1KΩ (102) ±5%")
      (footprint "0603_Rx4")
      (description "贴片排阻")
      (libsource (lib "Miscellaneous Devices LC") (part "0603*4  1KΩ (102) 5%"))
    )
    (comp (ref "RX1")
      (value "黄灯 0603")
      (footprint "0603_LED_S1")
      (description "发光二极管")
      (libsource (lib "Miscellaneous Devices LC") (part "0603 黄灯"))
    )
    (comp (ref "SW1")
      (value "3×6贴片轻触开关")
      (footprint "TECO-FSMSM-2_V")
      (description "FSMSM Push Button Switch, 50 mA, -35 to 85 degC, 2-Pin SMD, RoHS, Bulk")
      (fields (field (name "MANUFACTURER") "TE Connectivity"))
      (libsource (lib "Altium Content Vault") (part "SW-SPST-2_C"))
    )
    (comp (ref "SW2")
      (value "3×6贴片轻触开关")
      (footprint "TECO-FSMSM-2_V")
      (description "FSMSM Push Button Switch, 50 mA, -35 to 85 degC, 2-Pin SMD, RoHS, Bulk")
      (fields (field (name "MANUFACTURER") "TE Connectivity"))
      (libsource (lib "Altium Content Vault") (part "SW-SPST-2_C"))
    )
    (comp (ref "SW3")
      (value "3×6贴片轻触开关")
      (footprint "TECO-FSMSM-2_V")
      (description "FSMSM Push Button Switch, 50 mA, -35 to 85 degC, 2-Pin SMD, RoHS, Bulk")
      (fields (field (name "MANUFACTURER") "TE Connectivity"))
      (libsource (lib "Altium Content Vault") (part "SW-SPST-2_C"))
    )
    (comp (ref "TEST-HEADER")
      (value "Header 3X2")
      (footprint "HDR2X3")
      (description "Header, 3-Pin, Dual row")
      (fields (field (name "PUBLISHER") "Altium Limited"))
      (libsource (lib "Miscellaneous Connectors") (part "Header 3X2"))
    )
    (comp (ref "TEST-HEADER1")
      (value "Header 3X2")
      (footprint "HDR2X3")
      (description "Header, 3-Pin, Dual row")
      (fields (field (name "PUBLISHER") "Altium Limited"))
      (libsource (lib "Miscellaneous Connectors") (part "Header 3X2"))
    )
    (comp (ref "TX1")
      (value "黄灯 0603")
      (footprint "0603_LED_S1")
      (description "发光二极管")
      (libsource (lib "Miscellaneous Devices LC") (part "0603 黄灯"))
    )
    (comp (ref "U1")
      (value "LM358DR2G")
      (footprint "SOIC-8_150mil")
      (description "通用运放")
      (libsource (lib "Miscellaneous Devices LC") (part "LM358DR2G_[C7950]"))
    )
    (comp (ref "U2")
      (value "WS2812B")
      (footprint "ADA-RGB-1655_V")
      (fields (field (name "MANUFACTURER") "Adafruit-Industries-LLC"))
      (libsource (lib "Altium Content Vault") (part "ADA-RGB-1655-4"))
    )
    (comp (ref "U3")
      (value "WS2812B")
      (footprint "ADA-RGB-1655_V")
      (fields (field (name "MANUFACTURER") "Adafruit-Industries-LLC"))
      (libsource (lib "Altium Content Vault") (part "ADA-RGB-1655-4"))
    )
    (comp (ref "U4")
      (value "WS2812B")
      (footprint "ADA-RGB-1655_V")
      (fields (field (name "MANUFACTURER") "Adafruit-Industries-LLC"))
      (libsource (lib "Altium Content Vault") (part "ADA-RGB-1655-4"))
    )
    (comp (ref "U5")
      (value "WS2812B")
      (footprint "ADA-RGB-1655_V")
      (fields (field (name "MANUFACTURER") "Adafruit-Industries-LLC"))
      (libsource (lib "Altium Content Vault") (part "ADA-RGB-1655-4"))
    )
    (comp (ref "U6")
      (value "WS2812B")
      (footprint "ADA-RGB-1655_V")
      (fields (field (name "MANUFACTURER") "Adafruit-Industries-LLC"))
      (libsource (lib "Altium Content Vault") (part "ADA-RGB-1655-4"))
    )
    (comp (ref "U7")
      (value "WS2812B")
      (footprint "ADA-RGB-1655_V")
      (fields (field (name "MANUFACTURER") "Adafruit-Industries-LLC"))
      (libsource (lib "Altium Content Vault") (part "ADA-RGB-1655-4"))
    )
    (comp (ref "U8")
      (value "WS2812B")
      (footprint "ADA-RGB-1655_V")
      (fields (field (name "MANUFACTURER") "Adafruit-Industries-LLC"))
      (libsource (lib "Altium Content Vault") (part "ADA-RGB-1655-4"))
    )
    (comp (ref "U9")
      (value "WS2812B")
      (footprint "ADA-RGB-1655_V")
      (fields (field (name "MANUFACTURER") "Adafruit-Industries-LLC"))
      (libsource (lib "Altium Content Vault") (part "ADA-RGB-1655-4"))
    )
    (comp (ref "U10")
      (value "WS2812B")
      (footprint "ADA-RGB-1655_V")
      (fields (field (name "MANUFACTURER") "Adafruit-Industries-LLC"))
      (libsource (lib "Altium Content Vault") (part "ADA-RGB-1655-4"))
    )
    (comp (ref "U11")
      (value "ESP-WROOM-32")
      (footprint "OLMX-ESP-WROOM-32")
      (description "Espressif System, 2.7 to 3.6 V, -40 to 85 degC, 38-Pin SMD")
      (fields (field (name "MANUFACTURER") "Olimex"))
      (libsource (lib "Altium Content Vault") (part "OLMX-ESP-WROOM-32-38"))
    )
    (comp (ref "U12")
      (value "XB24CZ7RIS-004")
      (footprint "DIGI-XB24CZ7RIS-004-Module-37_V")
      (fields (field (name "MANUFACTURER") "Digi international"))
      (libsource (lib "Altium Content Vault") (part "DIGI-XB24CZ7RIS-004-Module-37"))
    )
    (comp (ref "U13")
      (value "SRV05-4HTG")
      (footprint "LFUS-SOT23-6_V")
      (description "Diode Array, 6 V, 10 A, -40 to 125 degC, 6-Pin SOT-23, RoHS, Tape and Reel")
      (fields (field (name "MANUFACTURER") "Littelfuse"))
      (libsource (lib "Altium Content Vault") (part "LFUS-SRV05-4HTG-SOT23-6"))
    )
    (comp (ref "U14")
      (value "SRV05-4HTG")
      (footprint "LFUS-SOT23-6_V")
      (description "Diode Array, 6 V, 10 A, -40 to 125 degC, 6-Pin SOT-23, RoHS, Tape and Reel")
      (fields (field (name "MANUFACTURER") "Littelfuse"))
      (libsource (lib "Altium Content Vault") (part "LFUS-SRV05-4HTG-SOT23-6"))
    )
    (comp (ref "U15")
      (value "POWERSTEP01")
      (footprint "STM-VFQFPN-102_V")
      (fields (field (name "MANUFACTURER") "STMicroelectronics"))
      (libsource (lib "Altium Content Vault") (part "STM-POWERSTEP01-102"))
    )
    (comp (ref "UART")
      (value "Header 3X2")
      (footprint "HDR2X3")
      (description "Header, 3-Pin, Dual row")
      (fields (field (name "PUBLISHER") "Altium Limited"))
      (libsource (lib "Miscellaneous Connectors") (part "Header 3X2"))
    )
    (comp (ref "X1")
      (value "Header 2")
      (footprint "HDR1X2")
      (description "Header, 2-Pin")
      (fields (field (name "PUBLISHER") "Altium Limited"))
      (libsource (lib "Miscellaneous Connectors") (part "Header 2"))
    )
    (comp (ref "Y1")
      (value "16MHZ 9PF 10PPM")
      (footprint "SMD-3225_4P")
      (description "贴片晶振")
      (libsource (lib "Miscellaneous Devices LC") (part "SMD-3225_4P  16MHZ 9PF 10PPM"))
    )
    (comp (ref "Y2")
      (value "CSTCE16M0V53-R0")
      (footprint "MURA-CSTCE_V-3_V")
      (fields (field (name "MANUFACTURER") "Murata"))
      (libsource (lib "Altium Content Vault") (part "MURA-CSTCE_V-3"))
    )
    (comp (ref "Z1")
      (value "CG0603MLC-05E")
      (footprint "BOUR-CG0603-2_V")
      (description "ESD Protector, 5 V Supply, -40 to 85 degC, 1.6 x 0.8 x 0.55 mm SMD, RoHS, Tape and Reel")
      (fields (field (name "MANUFACTURER") "Bourns"))
      (libsource (lib "Altium Content Vault") (part "BOUR-VSR-2"))
    )
    (comp (ref "Z2")
      (value "CG0603MLC-05E")
      (footprint "BOUR-CG0603-2_V")
      (description "ESD Protector, 5 V Supply, -40 to 85 degC, 1.6 x 0.8 x 0.55 mm SMD, RoHS, Tape and Reel")
      (fields (field (name "MANUFACTURER") "Bourns"))
      (libsource (lib "Altium Content Vault") (part "BOUR-VSR-2"))
    )
  )
  (nets
    (net (code "1") (name "+3.3V") (class "Default")
      (node (ref "C10") (pin "2") (pinfunction "2_2") (pintype "passive"))
      (node (ref "C29") (pin "1") (pinfunction "1_1") (pintype "passive"))
      (node (ref "C31") (pin "1") (pinfunction "1_1") (pintype "passive"))
      (node (ref "C34") (pin "1") (pinfunction "1_1") (pintype "passive"))
      (node (ref "C35") (pin "1") (pinfunction "1_1") (pintype "passive"))
      (node (ref "C41") (pin "2") (pinfunction "2_2") (pintype "passive"))
      (node (ref "C42") (pin "2") (pinfunction "2_2") (pintype "passive"))
      (node (ref "CP2104") (pin "5") (pinfunction "VIO_5") (pintype "power_in"))
      (node (ref "CP2104") (pin "6") (pinfunction "VDD_6") (pintype "power_in"))
      (node (ref "CP2104") (pin "7") (pinfunction "REGIN_7") (pintype "power_in"))
      (node (ref "CalibrationHeader") (pin "1") (pinfunction "1_1") (pintype "passive"))
      (node (ref "Camera") (pin "1") (pinfunction "1_1") (pintype "passive"))
      (node (ref "D4") (pin "A") (pinfunction "A_A") (pintype "passive"))
      (node (ref "D5") (pin "A") (pinfunction "A_A") (pintype "passive"))
      (node (ref "D6") (pin "A") (pinfunction "A_A") (pintype "passive"))
      (node (ref "D7") (pin "A") (pinfunction "A_A") (pintype "passive"))
      (node (ref "EEPROM") (pin "8") (pinfunction "VCC_8") (pintype "power_in"))
      (node (ref "IC3") (pin "5") (pinfunction "VOUT_5") (pintype "power_in"))
      (node (ref "R14") (pin "1") (pinfunction "1_1") (pintype "passive"))
      (node (ref "R17") (pin "2") (pinfunction "2_2") (pintype "passive"))
      (node (ref "R22") (pin "2") (pinfunction "2_2") (pintype "passive"))
      (node (ref "R24") (pin "2") (pinfunction "2_2") (pintype "passive"))
      (node (ref "R25") (pin "2") (pinfunction "2_2") (pintype "passive"))
      (node (ref "R26") (pin "2") (pinfunction "2_2") (pintype "passive"))
      (node (ref "TEST-HEADER") (pin "3") (pinfunction "3_3") (pintype "passive"))
      (node (ref "TEST-HEADER1") (pin "3") (pinfunction "3_3") (pintype "passive"))
      (node (ref "U1") (pin "6") (pinfunction "IN-_6") (pintype "input"))
      (node (ref "U11") (pin "2") (pinfunction "3V3_2") (pintype "power_in"))
      (node (ref "U12") (pin "2") (pinfunction "VCC_2") (pintype "power_in"))
      (node (ref "U14") (pin "5") (pinfunction "VCC_5") (pintype "power_in"))
      (node (ref "UART") (pin "1") (pinfunction "1_1") (pintype "passive"))
    )
    (net (code "2") (name "+5") (class "Default")
      (node (ref "C11") (pin "1") (pinfunction "1_1") (pintype "passive"))
      (node (ref "C19") (pin "1") (pinfunction "1_1") (pintype "passive"))
      (node (ref "C20") (pin "1") (pinfunction "1_1") (pintype "passive"))
      (node (ref "C21") (pin "1") (pinfunction "1_1") (pintype "passive"))
      (node (ref "C22") (pin "1") (pinfunction "1_1") (pintype "passive"))
      (node (ref "C23") (pin "1") (pinfunction "1_1") (pintype "passive"))
      (node (ref "C24") (pin "1") (pinfunction "1_1") (pintype "passive"))
      (node (ref "C25") (pin "1") (pinfunction "1_1") (pintype "passive"))
      (node (ref "C26") (pin "1") (pinfunction "1_1") (pintype "passive"))
      (node (ref "C27") (pin "1") (pinfunction "1_1") (pintype "passive"))
      (node (ref "C36") (pin "1") (pinfunction "1_1") (pintype "passive"))
      (node (ref "C37") (pin "1") (pinfunction "1_1") (pintype "passive"))
      (node (ref "C38") (pin "1") (pinfunction "1_1") (pintype "passive"))
      (node (ref "C39") (pin "1") (pinfunction "1_1") (pintype "passive"))
      (node (ref "C4") (pin "1") (pinfunction "1_1") (pintype "passive"))
      (node (ref "C7") (pin "1") (pinfunction "1_1") (pintype "passive"))
      (node (ref "C8") (pin "1") (pinfunction "1_1") (pintype "passive"))
      (node (ref "C9") (pin "1") (pinfunction "1_1") (pintype "passive"))
      (node (ref "D2") (pin "2") (pinfunction "K_2") (pintype "passive"))
      (node (ref "D3") (pin "2") (pinfunction "K_2") (pintype "passive"))
      (node (ref "IC1") (pin "2") (pinfunction "VOUT_2") (pintype "power_in"))
      (node (ref "IC1") (pin "4") (pinfunction "VOUT_4") (pintype "power_in"))
      (node (ref "IC2") (pin "10") (pinfunction "VCC_10") (pintype "power_in"))
      (node (ref "IC2") (pin "31") (pinfunction "VCC_31") (pintype "power_in"))
      (node (ref "IC2") (pin "61") (pinfunction "VCC_61") (pintype "power_in"))
      (node (ref "IC2") (pin "80") (pinfunction "VCC_80") (pintype "power_in"))
      (node (ref "IC3") (pin "1") (pinfunction "VIN_1") (pintype "power_in"))
      (node (ref "IC3") (pin "3") (pinfunction "ON/~{OFF}_3") (pintype "input"))
      (node (ref "ICSP1") (pin "2") (pinfunction "2_2") (pintype "passive"))
      (node (ref "ICSP2") (pin "2") (pinfunction "2_2") (pintype "passive"))
      (node (ref "L1") (pin "2") (pinfunction "2_2") (pintype "passive"))
      (node (ref "M1") (pin "13") (pinfunction "VM2_13") (pintype "power_in"))
      (node (ref "M1") (pin "14") (pinfunction "VM3_14") (pintype "power_in"))
      (node (ref "M1") (pin "20") (pinfunction "VCC_20") (pintype "power_in"))
      (node (ref "M1") (pin "24") (pinfunction "VM1_24") (pintype "power_in"))
      (node (ref "M2") (pin "13") (pinfunction "VM2_13") (pintype "power_in"))
      (node (ref "M2") (pin "14") (pinfunction "VM3_14") (pintype "power_in"))
      (node (ref "M2") (pin "20") (pinfunction "VCC_20") (pintype "power_in"))
      (node (ref "M2") (pin "24") (pinfunction "VM1_24") (pintype "power_in"))
      (node (ref "P1") (pin "2") (pinfunction "2_2") (pintype "passive"))
      (node (ref "Q1") (pin "2") (pinfunction "S_2") (pintype "passive"))
      (node (ref "R10") (pin "2") (pinfunction "2_2") (pintype "passive"))
      (node (ref "R11") (pin "2") (pinfunction "2_2") (pintype "passive"))
      (node (ref "R3") (pin "1") (pinfunction "1_1") (pintype "passive"))
      (node (ref "R7") (pin "1") (pinfunction "1_1") (pintype "passive"))
      (node (ref "R8") (pin "1") (pinfunction "1_1") (pintype "passive"))
      (node (ref "Rp1") (pin "1") (pinfunction "1_1") (pintype "passive"))
      (node (ref "Rp1") (pin "2") (pinfunction "2_2") (pintype "passive"))
      (node (ref "TEST-HEADER") (pin "5") (pinfunction "5_5") (pintype "passive"))
      (node (ref "TEST-HEADER1") (pin "5") (pinfunction "5_5") (pintype "passive"))
      (node (ref "U1") (pin "8") (pinfunction "V+_8") (pintype "power_in"))
      (node (ref "U10") (pin "1") (pinfunction "VDD_1") (pintype "power_in"))
      (node (ref "U13") (pin "5") (pinfunction "VCC_5") (pintype "power_in"))
      (node (ref "U2") (pin "1") (pinfunction "VDD_1") (pintype "power_in"))
      (node (ref "U3") (pin "1") (pinfunction "VDD_1") (pintype "power_in"))
      (node (ref "U4") (pin "1") (pinfunction "VDD_1") (pintype "power_in"))
      (node (ref "U5") (pin "1") (pinfunction "VDD_1") (pintype "power_in"))
      (node (ref "U6") (pin "1") (pinfunction "VDD_1") (pintype "power_in"))
      (node (ref "U7") (pin "1") (pinfunction "VDD_1") (pintype "power_in"))
      (node (ref "U8") (pin "1") (pinfunction "VDD_1") (pintype "power_in"))
      (node (ref "U9") (pin "1") (pinfunction "VDD_1") (pintype "power_in"))
    )
    (net (code "3") (name "+12") (class "Default")
      (node (ref "C-BOOT") (pin "1") (pinfunction "1_1") (pintype "passive"))
      (node (ref "C-VS") (pin "2") (pinfunction "2_2") (pintype "passive"))
      (node (ref "C-VSREG") (pin "1") (pinfunction "1_1") (pintype "passive"))
      (node (ref "C40") (pin "1") (pinfunction "1_1") (pintype "passive"))
      (node (ref "D1") (pin "1") (pinfunction "A_1") (pintype "passive"))
      (node (ref "D8") (pin "1") (pinfunction "A_1") (pintype "passive"))
      (node (ref "P3") (pin "1") (pinfunction "1_1") (pintype "passive"))
      (node (ref "P4") (pin "1") (pinfunction "1_1") (pintype "passive"))
      (node (ref "POWER") (pin "2") (pinfunction "2_2") (pintype "passive"))
      (node (ref "POWER") (pin "4") (pinfunction "4_4") (pintype "passive"))
      (node (ref "POWER") (pin "6") (pinfunction "6_6") (pintype "passive"))
      (node (ref "RB") (pin "2") (pinfunction "2_2") (pintype "passive"))
      (node (ref "U15") (pin "1") (pinfunction "VS_1") (pintype "power_in"))
      (node (ref "U15") (pin "2") (pinfunction "VS_2") (pintype "power_in"))
      (node (ref "U15") (pin "23") (pinfunction "VS_23") (pintype "power_in"))
      (node (ref "U15") (pin "24") (pinfunction "VS_24") (pintype "power_in"))
      (node (ref "U15") (pin "25") (pinfunction "VS_25") (pintype "power_in"))
      (node (ref "U15") (pin "26") (pinfunction "VS_26") (pintype "power_in"))
      (node (ref "U15") (pin "27") (pinfunction "VS_27") (pintype "power_in"))
      (node (ref "U15") (pin "28") (pinfunction "VS_28") (pintype "power_in"))
      (node (ref "U15") (pin "29") (pinfunction "VS_29") (pintype "power_in"))
      (node (ref "U15") (pin "3") (pinfunction "VS_3") (pintype "power_in"))
      (node (ref "U15") (pin "30") (pinfunction "VS_30") (pintype "power_in"))
      (node (ref "U15") (pin "31") (pinfunction "VS_31") (pintype "power_in"))
      (node (ref "U15") (pin "32") (pinfunction "VS_32") (pintype "power_in"))
      (node (ref "U15") (pin "4") (pinfunction "VS_4") (pintype "power_in"))
      (node (ref "U15") (pin "43") (pinfunction "VS_43") (pintype "power_in"))
      (node (ref "U15") (pin "44") (pinfunction "VS_44") (pintype "power_in"))
      (node (ref "U15") (pin "45") (pinfunction "VS_45") (pintype "power_in"))
      (node (ref "U15") (pin "46") (pinfunction "VS_46") (pintype "power_in"))
      (node (ref "U15") (pin "47") (pinfunction "VS_47") (pintype "power_in"))
      (node (ref "U15") (pin "48") (pinfunction "VS_48") (pintype "power_in"))
      (node (ref "U15") (pin "49") (pinfunction "VS_49") (pintype "power_in"))
      (node (ref "U15") (pin "5") (pinfunction "VS_5") (pintype "power_in"))
      (node (ref "U15") (pin "50") (pinfunction "VS_50") (pintype "power_in"))
      (node (ref "U15") (pin "51") (pinfunction "VS_51") (pintype "power_in"))
      (node (ref "U15") (pin "52") (pinfunction "VS_52") (pintype "power_in"))
      (node (ref "U15") (pin "55") (pinfunction "VS_55") (pintype "power_in"))
      (node (ref "U15") (pin "6") (pinfunction "VS_6") (pintype "power_in"))
      (node (ref "U15") (pin "61") (pinfunction "VSREG_61") (pintype "power_in"))
      (node (ref "U15") (pin "66") (pinfunction "VS_66") (pintype "power_in"))
      (node (ref "U15") (pin "67") (pinfunction "VS_67") (pintype "power_in"))
      (node (ref "U15") (pin "68") (pinfunction "VS_68") (pintype "power_in"))
      (node (ref "U15") (pin "69") (pinfunction "VS_69") (pintype "power_in"))
      (node (ref "U15") (pin "70") (pinfunction "VS_70") (pintype "power_in"))
      (node (ref "U15") (pin "71") (pinfunction "VS_71") (pintype "power_in"))
      (node (ref "U15") (pin "72") (pinfunction "VS_72") (pintype "power_in"))
      (node (ref "U15") (pin "73") (pinfunction "VS_73") (pintype "power_in"))
      (node (ref "U15") (pin "74") (pinfunction "VS_74") (pintype "power_in"))
      (node (ref "U15") (pin "75") (pinfunction "VS_75") (pintype "power_in"))
      (node (ref "U15") (pin "86") (pinfunction "VS_86") (pintype "power_in"))
      (node (ref "U15") (pin "87") (pinfunction "VS_87") (pintype "power_in"))
      (node (ref "U15") (pin "88") (pinfunction "VS_88") (pintype "power_in"))
      (node (ref "U15") (pin "89") (pinfunction "VS_89") (pintype "power_in"))
      (node (ref "U15") (pin "90") (pinfunction "VS_90") (pintype "power_in"))
      (node (ref "U15") (pin "91") (pinfunction "VS_91") (pintype "power_in"))
      (node (ref "U15") (pin "94") (pinfunction "VS_94") (pintype "power_in"))
      (node (ref "U15") (pin "95") (pinfunction "VS_95") (pintype "power_in"))
      (node (ref "X1") (pin "2") (pinfunction "2_2") (pintype "passive"))
    )
    (net (code "4") (name "/2WIRE-SCK") (class "Default")
      (node (ref "CalibrationHeader") (pin "3") (pinfunction "3_3") (pintype "passive"))
      (node (ref "Camera") (pin "3") (pinfunction "3_3") (pintype "passive"))
      (node (ref "IC2") (pin "43") (pinfunction "PD0_(SCL/INT0)_43") (pintype "bidirectional"))
      (node (ref "P21") (pin "8") (pinfunction "8_8") (pintype "passive"))
      (node (ref "R23") (pin "1") (pinfunction "1_1") (pintype "passive"))
      (node (ref "R7") (pin "2") (pinfunction "2_2") (pintype "passive"))
    )
    (net (code "5") (name "/2WIRE-SDIO") (class "Default")
      (node (ref "CalibrationHeader") (pin "4") (pinfunction "4_4") (pintype "passive"))
      (node (ref "Camera") (pin "4") (pinfunction "4_4") (pintype "passive"))
      (node (ref "IC2") (pin "44") (pinfunction "PD1_(SDA/INT1)_44") (pintype "bidirectional"))
      (node (ref "P21") (pin "7") (pinfunction "7_7") (pintype "passive"))
      (node (ref "R22") (pin "1") (pinfunction "1_1") (pintype "passive"))
      (node (ref "R8") (pin "2") (pinfunction "2_2") (pintype "passive"))
    )
    (net (code "6") (name "/ADCIN") (class "Default")
      (node (ref "RA") (pin "2") (pinfunction "2_2") (pintype "passive"))
      (node (ref "RB") (pin "1") (pinfunction "1_1") (pintype "passive"))
      (node (ref "U15") (pin "54") (pinfunction "ADCIN_54") (pintype "input"))
    )
    (net (code "7") (name "/AIN1") (class "Default")
      (node (ref "IC2") (pin "78") (pinfunction "PA0_(AD0)_78") (pintype "bidirectional"))
      (node (ref "M1") (pin "21") (pinfunction "AIN1_21") (pintype "input"))
      (node (ref "P18") (pin "1") (pinfunction "1_1") (pintype "passive"))
    )
    (net (code "8") (name "/AIN2") (class "Default")
      (node (ref "IC2") (pin "77") (pinfunction "PA1_(AD1)_77") (pintype "bidirectional"))
      (node (ref "M1") (pin "22") (pinfunction "AIN2_22") (pintype "input"))
      (node (ref "P18") (pin "2") (pinfunction "2_2") (pintype "passive"))
    )
    (net (code "9") (name "/AREF") (class "Default")
      (node (ref "C13") (pin "1") (pinfunction "1_1") (pintype "passive"))
      (node (ref "IC2") (pin "98") (pinfunction "AREF_98") (pintype "power_in"))
    )
    (net (code "10") (name "/AVCC") (class "Default")
      (node (ref "C6") (pin "1") (pinfunction "1_1") (pintype "passive"))
      (node (ref "IC2") (pin "100") (pinfunction "AVCC_100") (pintype "power_in"))
      (node (ref "L1") (pin "1") (pinfunction "1_1") (pintype "passive"))
    )
    (net (code "11") (name "/BIN1") (class "Default")
      (node (ref "IC2") (pin "76") (pinfunction "PA2_(AD2)_76") (pintype "bidirectional"))
      (node (ref "M1") (pin "17") (pinfunction "BIN1_17") (pintype "input"))
      (node (ref "P18") (pin "3") (pinfunction "3_3") (pintype "passive"))
    )
    (net (code "12") (name "/BIN2") (class "Default")
      (node (ref "IC2") (pin "75") (pinfunction "PA3_(AD3)_75") (pintype "bidirectional"))
      (node (ref "M1") (pin "16") (pinfunction "BIN2_16") (pintype "input"))
      (node (ref "P18") (pin "4") (pinfunction "4_4") (pintype "passive"))
    )
    (net (code "13") (name "/BUSY") (class "Default")
      (node (ref "P13") (pin "3") (pinfunction "3_3") (pintype "passive"))
      (node (ref "R20") (pin "1") (pinfunction "1_1") (pintype "passive"))
      (node (ref "U15") (pin "15") (pinfunction "BUSY/SYNC_15") (pintype "open_collector"))
    )
    (net (code "14") (name "/CIN1") (class "Default")
      (node (ref "IC2") (pin "74") (pinfunction "PA4_(AD4)_74") (pintype "bidirectional"))
      (node (ref "M2") (pin "21") (pinfunction "AIN1_21") (pintype "input"))
      (node (ref "P18") (pin "5") (pinfunction "5_5") (pintype "passive"))
    )
    (net (code "15") (name "/CIN2") (class "Default")
      (node (ref "IC2") (pin "73") (pinfunction "PA5_(AD5)_73") (pintype "bidirectional"))
      (node (ref "M2") (pin "22") (pinfunction "AIN2_22") (pintype "input"))
      (node (ref "P18") (pin "6") (pinfunction "6_6") (pintype "passive"))
    )
    (net (code "16") (name "/CK") (class "Default")
      (node (ref "P20") (pin "1") (pinfunction "1_1") (pintype "passive"))
      (node (ref "P7") (pin "2") (pinfunction "2_2") (pintype "passive"))
      (node (ref "U11") (pin "20") (pinfunction "SCK/CLK_20") (pintype "bidirectional"))
      (node (ref "U15") (pin "11") (pinfunction "CK_11") (pintype "input"))
    )
    (net (code "17") (name "/CMP") (class "Default")
      (node (ref "C12") (pin "1") (pinfunction "1_1") (pintype "passive"))
      (node (ref "R4") (pin "1") (pinfunction "1_1") (pintype "passive"))
      (node (ref "R5") (pin "2") (pinfunction "2_2") (pintype "passive"))
      (node (ref "U1") (pin "5") (pinfunction "IN+_5") (pintype "input"))
    )
    (net (code "18") (name "/CP") (class "Default")
      (node (ref "C-FLY") (pin "2") (pinfunction "2_2") (pintype "passive"))
      (node (ref "U15") (pin "57") (pinfunction "CP_57") (pintype "output"))
    )
    (net (code "19") (name "/CS") (class "Default")
      (node (ref "P20") (pin "6") (pinfunction "6_6") (pintype "passive"))
      (node (ref "P7") (pin "1") (pinfunction "1_1") (pintype "passive"))
      (node (ref "U11") (pin "19") (pinfunction "SCS/CMD_19") (pintype "bidirectional"))
      (node (ref "U15") (pin "10") (pinfunction "CS_10") (pintype "input"))
    )
    (net (code "20") (name "/D+") (class "Default")
      (node (ref "J1") (pin "3") (pinfunction "D+_3") (pintype "passive"))
      (node (ref "J2") (pin "A6") (pinfunction "Dp1_A6") (pintype "passive"))
      (node (ref "J2") (pin "B6") (pinfunction "Dp2_B6") (pintype "passive"))
      (node (ref "R2") (pin "1") (pinfunction "1_1") (pintype "passive"))
      (node (ref "Z2") (pin "2") (pinfunction "2_2") (pintype "passive"))
    )
    (net (code "21") (name "/D-") (class "Default")
      (node (ref "J1") (pin "2") (pinfunction "D-_2") (pintype "passive"))
      (node (ref "J2") (pin "A7") (pinfunction "Dn1_A7") (pintype "passive"))
      (node (ref "J2") (pin "B7") (pinfunction "Dn2_B7") (pintype "passive"))
      (node (ref "R1") (pin "1") (pinfunction "1_1") (pintype "passive"))
      (node (ref "Z1") (pin "2") (pinfunction "2_2") (pintype "passive"))
    )
    (net (code "22") (name "/D2+") (class "Default")
      (node (ref "CP2104") (pin "3") (pinfunction "D+_3") (pintype "bidirectional"))
      (node (ref "J3") (pin "3") (pinfunction "D+_3") (pintype "passive"))
      (node (ref "J4") (pin "A6") (pinfunction "Dp1_A6") (pintype "passive"))
      (node (ref "J4") (pin "B6") (pinfunction "Dp2_B6") (pintype "passive"))
      (node (ref "U13") (pin "3") (pinfunction "I/O_2_3") (pintype "passive"))
      (node (ref "U13") (pin "4") (pinfunction "I/O_3_4") (pintype "passive"))
    )
    (net (code "23") (name "/D2-") (class "Default")
      (node (ref "CP2104") (pin "4") (pinfunction "D-_4") (pintype "bidirectional"))
      (node (ref "J3") (pin "2") (pinfunction "D-_2") (pintype "passive"))
      (node (ref "J4") (pin "A7") (pinfunction "Dn1_A7") (pintype "passive"))
      (node (ref "J4") (pin "B7") (pinfunction "Dn2_B7") (pintype "passive"))
      (node (ref "U13") (pin "1") (pinfunction "I/O_1_1") (pintype "passive"))
      (node (ref "U13") (pin "6") (pinfunction "I/O_4_6") (pintype "passive"))
    )
    (net (code "24") (name "/D3") (class "Default")
      (node (ref "IC2") (pin "46") (pinfunction "PD3_(TXD1/INT3)_46") (pintype "bidirectional"))
      (node (ref "IC2") (pin "7") (pinfunction "PE5_(OC3C/INT5)_7") (pintype "bidirectional"))
      (node (ref "P1") (pin "3") (pinfunction "3_3") (pintype "passive"))
      (node (ref "P14") (pin "3") (pinfunction "3_3") (pintype "passive"))
      (node (ref "P21") (pin "5") (pinfunction "5_5") (pintype "passive"))
      (node (ref "TEST-HEADER1") (pin "2") (pinfunction "2_2") (pintype "passive"))
      (node (ref "U12") (pin "4") (pinfunction "DIN/~{CONFIG}/DIO14_4") (pintype "bidirectional"))
      (node (ref "U2") (pin "4") (pinfunction "DIN_4") (pintype "input"))
    )
    (net (code "25") (name "/D6") (class "Default")
      (node (ref "IC2") (pin "15") (pinfunction "PH3_(OC4A)_15") (pintype "bidirectional"))
      (node (ref "M1") (pin "23") (pinfunction "PWMA_23") (pintype "input"))
      (node (ref "P16") (pin "5") (pinfunction "5_5") (pintype "passive"))
    )
    (net (code "26") (name "/D7") (class "Default")
      (node (ref "IC2") (pin "16") (pinfunction "PH4_(OC4B)_16") (pintype "bidirectional"))
      (node (ref "M1") (pin "15") (pinfunction "PWMB_15") (pintype "input"))
      (node (ref "P16") (pin "4") (pinfunction "4_4") (pintype "passive"))
    )
    (net (code "27") (name "/D8") (class "Default")
      (node (ref "IC2") (pin "17") (pinfunction "PH5_(OC4C)_17") (pintype "bidirectional"))
      (node (ref "M2") (pin "23") (pinfunction "PWMA_23") (pintype "input"))
      (node (ref "P16") (pin "3") (pinfunction "3_3") (pintype "passive"))
    )
    (net (code "28") (name "/D9") (class "Default")
      (node (ref "IC2") (pin "18") (pinfunction "PH6_(OC2B)_18") (pintype "bidirectional"))
      (node (ref "M2") (pin "15") (pinfunction "PWMB_15") (pintype "input"))
      (node (ref "P16") (pin "2") (pinfunction "2_2") (pintype "passive"))
    )
    (net (code "29") (name "/D28") (class "Default")
      (node (ref "IC2") (pin "72") (pinfunction "PA6_(AD6)_72") (pintype "bidirectional"))
      (node (ref "M2") (pin "17") (pinfunction "BIN1_17") (pintype "input"))
      (node (ref "P18") (pin "7") (pinfunction "7_7") (pintype "passive"))
    )
    (net (code "30") (name "/D29") (class "Default")
      (node (ref "IC2") (pin "71") (pinfunction "PA7_(AD7)_71") (pintype "bidirectional"))
      (node (ref "M2") (pin "16") (pinfunction "BIN2_16") (pintype "input"))
      (node (ref "P18") (pin "8") (pinfunction "8_8") (pintype "passive"))
    )
    (net (code "31") (name "/D39") (class "Default")
      (node (ref "IC2") (pin "70") (pinfunction "PG2_(ALE)_70") (pintype "bidirectional"))
      (node (ref "M1") (pin "19") (pinfunction "STBY_19") (pintype "input"))
      (node (ref "M2") (pin "19") (pinfunction "STBY_19") (pintype "input"))
      (node (ref "P13") (pin "2") (pinfunction "2_2") (pintype "passive"))
      (node (ref "P24") (pin "3") (pinfunction "3_3") (pintype "passive"))
      (node (ref "U15") (pin "19") (pinfunction "STBY/RESET_19") (pintype "input"))
    )
    (net (code "32") (name "/DOUT") (class "Default")
      (node (ref "IC2") (pin "45") (pinfunction "PD2_(RXD1/INT2)_45") (pintype "bidirectional"))
      (node (ref "P21") (pin "6") (pinfunction "6_6") (pintype "passive"))
      (node (ref "TEST-HEADER1") (pin "4") (pinfunction "4_4") (pintype "passive"))
      (node (ref "U12") (pin "3") (pinfunction "DOUT/DIO13_3") (pintype "bidirectional"))
    )
    (net (code "33") (name "/DTR") (class "Default")
      (node (ref "C18") (pin "1") (pinfunction "1_1") (pintype "passive"))
      (node (ref "CP2104") (pin "23") (pinfunction "~{DTR}_23") (pintype "output"))
      (node (ref "IC4") (pin "13") (pinfunction "PD7_(~{CTS}/~{HWB}/AIN6/T0/INT7)_13") (pintype "bidirectional"))
      (node (ref "Q3") (pin "2") (pinfunction "E_2") (pintype "passive"))
      (node (ref "R13") (pin "2") (pinfunction "2_2") (pintype "passive"))
      (node (ref "R18") (pin "1") (pinfunction "1_1") (pintype "passive"))
    )
    (net (code "34") (name "/E2PROM-SCK") (class "Default")
      (node (ref "CalibrationHeader") (pin "6") (pinfunction "6_6") (pintype "passive"))
      (node (ref "Camera") (pin "7") (pinfunction "7_7") (pintype "passive"))
      (node (ref "EEPROM") (pin "6") (pinfunction "SCL_6") (pintype "input"))
      (node (ref "R25") (pin "1") (pinfunction "1_1") (pintype "passive"))
    )
    (net (code "35") (name "/E2PROM-SDA") (class "Default")
      (node (ref "CalibrationHeader") (pin "7") (pinfunction "7_7") (pintype "passive"))
      (node (ref "Camera") (pin "8") (pinfunction "8_8") (pintype "passive"))
      (node (ref "EEPROM") (pin "5") (pinfunction "SDA_5") (pintype "bidirectional"))
      (node (ref "R26") (pin "1") (pinfunction "1_1") (pintype "passive"))
    )
    (net (code "36") (name "/EFUSE") (class "Default")
      (node (ref "CalibrationHeader") (pin "5") (pinfunction "5_5") (pintype "passive"))
      (node (ref "Camera") (pin "5") (pinfunction "5_5") (pintype "passive"))
    )
    (net (code "37") (name "/ESP32-EN") (class "Default")
      (node (ref "C28") (pin "2") (pinfunction "2_2") (pintype "passive"))
      (node (ref "C32") (pin "1") (pinfunction "1_1") (pintype "passive"))
      (node (ref "P23") (pin "3") (pinfunction "3_3") (pintype "passive"))
      (node (ref "Q2") (pin "3") (pinfunction "C_3") (pintype "passive"))
      (node (ref "R14") (pin "2") (pinfunction "2_2") (pintype "passive"))
      (node (ref "Rp3") (pin "7") (pinfunction "7_7") (pintype "passive"))
      (node (ref "SW1") (pin "2") (pinfunction "2_2") (pintype "passive"))
      (node (ref "U11") (pin "3") (pinfunction "EN_3") (pintype "input"))
      (node (ref "U14") (pin "1") (pinfunction "I/O_1_1") (pintype "passive"))
      (node (ref "UART") (pin "6") (pinfunction "6_6") (pintype "passive"))
    )
    (net (code "38") (name "/FLAG") (class "Default")
      (node (ref "P13") (pin "4") (pinfunction "4_4") (pintype "passive"))
      (node (ref "R21") (pin "1") (pinfunction "1_1") (pintype "passive"))
      (node (ref "U15") (pin "16") (pinfunction "FLAG_16") (pintype "open_collector"))
    )
    (net (code "39") (name "/GATE_CMD") (class "Default")
      (node (ref "Q1") (pin "1") (pinfunction "G_1") (pintype "passive"))
      (node (ref "U1") (pin "7") (pinfunction "OUT_7") (pintype "output"))
    )
    (net (code "40") (name "/IO0") (class "Default")
      (node (ref "C30") (pin "2") (pinfunction "2_2") (pintype "passive"))
      (node (ref "PIN-OUT") (pin "22") (pinfunction "22_22") (pintype "passive"))
      (node (ref "Q3") (pin "3") (pinfunction "C_3") (pintype "passive"))
      (node (ref "Rp3") (pin "8") (pinfunction "8_8") (pintype "passive"))
      (node (ref "SW2") (pin "2") (pinfunction "2_2") (pintype "passive"))
      (node (ref "U11") (pin "25") (pinfunction "IO0_25") (pintype "bidirectional"))
      (node (ref "U14") (pin "6") (pinfunction "I/O_4_6") (pintype "passive"))
      (node (ref "UART") (pin "4") (pinfunction "4_4") (pintype "passive"))
    )
    (net (code "41") (name "/M8RXD") (class "Default")
      (node (ref "IC4") (pin "9") (pinfunction "PD3_(TXD1/INT3)_9") (pintype "bidirectional"))
      (node (ref "Rp1") (pin "4") (pinfunction "4_4") (pintype "passive"))
    )
    (net (code "42") (name "/M8TXD") (class "Default")
      (node (ref "IC4") (pin "8") (pinfunction "PD2_(RXD1/AIN1/INT2)_8") (pintype "bidirectional"))
      (node (ref "Rp1") (pin "3") (pinfunction "3_3") (pintype "passive"))
    )
    (net (code "43") (name "/MISO") (class "Default")
      (node (ref "IC2") (pin "22") (pinfunction "PB3_(MISO/PCINT3)_22") (pintype "bidirectional"))
      (node (ref "ICSP1") (pin "1") (pinfunction "1_1") (pintype "passive"))
      (node (ref "P17") (pin "5") (pinfunction "5_5") (pintype "passive"))
    )
    (net (code "44") (name "/MISO2") (class "Default")
      (node (ref "IC4") (pin "17") (pinfunction "PB3_(PDO/MISO/PCINT3)_17") (pintype "bidirectional"))
      (node (ref "ICSP2") (pin "1") (pinfunction "1_1") (pintype "passive"))
    )
    (net (code "45") (name "/MOSI") (class "Default")
      (node (ref "IC2") (pin "21") (pinfunction "PB2_(MOSI/PCINT2)_21") (pintype "bidirectional"))
      (node (ref "ICSP1") (pin "4") (pinfunction "4_4") (pintype "passive"))
      (node (ref "P17") (pin "6") (pinfunction "6_6") (pintype "passive"))
    )
    (net (code "46") (name "/MOSI2") (class "Default")
      (node (ref "IC4") (pin "16") (pinfunction "PB2_(PDI/MOSI/PCINT2)_16") (pintype "bidirectional"))
      (node (ref "ICSP2") (pin "4") (pinfunction "4_4") (pintype "passive"))
    )
    (net (code "47") (name "/MTCK") (class "Default")
      (node (ref "PIN-OUT") (pin "17") (pinfunction "17_17") (pintype "passive"))
      (node (ref "Rp2") (pin "6") (pinfunction "6_6") (pintype "passive"))
      (node (ref "U11") (pin "16") (pinfunction "IO13_16") (pintype "bidirectional"))
    )
    (net (code "48") (name "/MTDI") (class "Default")
      (node (ref "PIN-OUT") (pin "18") (pinfunction "18_18") (pintype "passive"))
      (node (ref "Rp2") (pin "7") (pinfunction "7_7") (pintype "passive"))
      (node (ref "U11") (pin "14") (pinfunction "IO12_14") (pintype "bidirectional"))
    )
    (net (code "49") (name "/MTDO") (class "Default")
      (node (ref "PIN-OUT") (pin "15") (pinfunction "15_15") (pintype "passive"))
      (node (ref "Rp2") (pin "5") (pinfunction "5_5") (pintype "passive"))
      (node (ref "U11") (pin "23") (pinfunction "IO15_23") (pintype "bidirectional"))
    )
    (net (code "50") (name "/MTMS") (class "Default")
      (node (ref "PIN-OUT") (pin "16") (pinfunction "16_16") (pintype "passive"))
      (node (ref "Rp2") (pin "8") (pinfunction "8_8") (pintype "passive"))
      (node (ref "U11") (pin "13") (pinfunction "IO14_13") (pintype "bidirectional"))
    )
    (net (code "51") (name "/MU-XTAL1") (class "Default")
      (node (ref "C16") (pin "1") (pinfunction "1_1") (pintype "passive"))
      (node (ref "IC4") (pin "1") (pinfunction "XTAL1_1") (pintype "input"))
      (node (ref "R9") (pin "2") (pinfunction "2_2") (pintype "passive"))
      (node (ref "Y1") (pin "3") (pinfunction "OSC2_3") (pintype "passive"))
    )
    (net (code "52") (name "/MU-XTAL2") (class "Default")
      (node (ref "C15") (pin "2") (pinfunction "2_2") (pintype "passive"))
      (node (ref "IC4") (pin "2") (pinfunction "(PC0)_XTAL2_2") (pintype "bidirectional"))
      (node (ref "R9") (pin "1") (pinfunction "1_1") (pintype "passive"))
      (node (ref "Y1") (pin "1") (pinfunction "OSC1_1") (pintype "passive"))
    )
    (net (code "53") (name "/PB7") (class "Default")
      (node (ref "IC2") (pin "26") (pinfunction "PB7_(OC0A/OC1C/PCINT7)_26") (pintype "bidirectional"))
      (node (ref "P17") (pin "1") (pinfunction "1_1") (pintype "passive"))
      (node (ref "U1") (pin "3") (pinfunction "IN+_3") (pintype "input"))
    )
    (net (code "54") (name "/RD+") (class "Default")
      (node (ref "IC4") (pin "30") (pinfunction "D-_30") (pintype "bidirectional"))
      (node (ref "R2") (pin "2") (pinfunction "2_2") (pintype "passive"))
    )
    (net (code "55") (name "/RD-") (class "Default")
      (node (ref "IC4") (pin "29") (pinfunction "D+_29") (pintype "bidirectional"))
      (node (ref "R1") (pin "2") (pinfunction "2_2") (pintype "passive"))
    )
    (net (code "56") (name "/RESET") (class "Default")
      (node (ref "C17") (pin "2") (pinfunction "2_2") (pintype "passive"))
      (node (ref "C18") (pin "2") (pinfunction "2_2") (pintype "passive"))
      (node (ref "D2") (pin "1") (pinfunction "A_1") (pintype "passive"))
      (node (ref "IC2") (pin "30") (pinfunction "~{RESET}_30") (pintype "input"))
      (node (ref "ICSP1") (pin "5") (pinfunction "5_5") (pintype "passive"))
      (node (ref "R10") (pin "1") (pinfunction "1_1") (pintype "passive"))
      (node (ref "RESET-EN1") (pin "1") (pinfunction "1_1") (pintype "passive"))
      (node (ref "RESET-EN1") (pin "2") (pinfunction "2_2") (pintype "passive"))
      (node (ref "RESET1") (pin "2") (pinfunction "2_2") (pintype "passive"))
      (node (ref "RESET1") (pin "4") (pinfunction "4_4") (pintype "passive"))
    )
    (net (code "57") (name "/RESET2") (class "Default")
      (node (ref "D3") (pin "1") (pinfunction "A_1") (pintype "passive"))
      (node (ref "IC4") (pin "24") (pinfunction "~{Reset}_(PC1/dW)_24") (pintype "bidirectional"))
      (node (ref "ICSP2") (pin "5") (pinfunction "5_5") (pintype "passive"))
      (node (ref "R11") (pin "1") (pinfunction "1_1") (pintype "passive"))
    )
    (net (code "58") (name "/RTS") (class "Default")
      (node (ref "CP2104") (pin "19") (pinfunction "~{RTS}_19") (pintype "output"))
      (node (ref "Q2") (pin "2") (pinfunction "E_2") (pintype "passive"))
      (node (ref "R19") (pin "1") (pinfunction "1_1") (pintype "passive"))
    )
    (net (code "59") (name "/RX0") (class "Default")
      (node (ref "IC2") (pin "2") (pinfunction "PE0_(RXD0/PCINT8)_2") (pintype "bidirectional"))
      (node (ref "P14") (pin "8") (pinfunction "8_8") (pintype "passive"))
      (node (ref "Rp1") (pin "5") (pinfunction "5_5") (pintype "passive"))
    )
    (net (code "60") (name "/RX2") (class "Default")
      (node (ref "IC2") (pin "12") (pinfunction "PH0_(RXD2)_12") (pintype "bidirectional"))
      (node (ref "P16") (pin "8") (pinfunction "8_8") (pintype "passive"))
      (node (ref "P20") (pin "5") (pinfunction "5_5") (pintype "passive"))
      (node (ref "U11") (pin "18") (pinfunction "SWP/SD3_18") (pintype "bidirectional"))
    )
    (net (code "61") (name "/RX3") (class "Default")
      (node (ref "IC2") (pin "63") (pinfunction "PJ0_(RXD3/PCINT9)_63") (pintype "bidirectional"))
      (node (ref "P18") (pin "17") (pinfunction "17_17") (pintype "passive"))
      (node (ref "TEST-HEADER") (pin "4") (pinfunction "4_4") (pintype "passive"))
    )
    (net (code "62") (name "/RXD") (class "Default")
      (node (ref "CP2104") (pin "20") (pinfunction "RXD_20") (pintype "input"))
      (node (ref "EN2") (pin "1") (pinfunction "1_1") (pintype "passive"))
      (node (ref "Rp3") (pin "6") (pinfunction "6_6") (pintype "passive"))
      (node (ref "U14") (pin "3") (pinfunction "I/O_2_3") (pintype "passive"))
      (node (ref "UART") (pin "3") (pinfunction "3_3") (pintype "passive"))
    )
    (net (code "63") (name "/RXD0") (class "Default")
      (node (ref "EN1") (pin "2") (pinfunction "2_2") (pintype "passive"))
      (node (ref "P23") (pin "1") (pinfunction "1_1") (pintype "passive"))
      (node (ref "U11") (pin "34") (pinfunction "RXD0_34") (pintype "bidirectional"))
    )
    (net (code "64") (name "/RXL") (class "Default")
      (node (ref "IC4") (pin "10") (pinfunction "PD4_(INT5/AIN3)_10") (pintype "bidirectional"))
      (node (ref "RX1") (pin "K") (pinfunction "K_K") (pintype "passive"))
    )
    (net (code "65") (name "/SCK") (class "Default")
      (node (ref "IC2") (pin "20") (pinfunction "PB1_(SCK/PCINT1)_20") (pintype "bidirectional"))
      (node (ref "ICSP1") (pin "3") (pinfunction "3_3") (pintype "passive"))
      (node (ref "P17") (pin "7") (pinfunction "7_7") (pintype "passive"))
    )
    (net (code "66") (name "/SCK2") (class "Default")
      (node (ref "IC4") (pin "15") (pinfunction "PB1_(SCLK/PCINT1)_15") (pintype "bidirectional"))
      (node (ref "ICSP2") (pin "3") (pinfunction "3_3") (pintype "passive"))
    )
    (net (code "67") (name "/SDI") (class "Default")
      (node (ref "P20") (pin "2") (pinfunction "2_2") (pintype "passive"))
      (node (ref "P7") (pin "4") (pinfunction "4_4") (pintype "passive"))
      (node (ref "U11") (pin "21") (pinfunction "SDO/SD0_21") (pintype "bidirectional"))
      (node (ref "U15") (pin "12") (pinfunction "SDI_12") (pintype "input"))
    )
    (net (code "68") (name "/SDO") (class "Default")
      (node (ref "P20") (pin "3") (pinfunction "3_3") (pintype "passive"))
      (node (ref "P7") (pin "3") (pinfunction "3_3") (pintype "passive"))
      (node (ref "U11") (pin "22") (pinfunction "SDI/SD1_22") (pintype "bidirectional"))
      (node (ref "U15") (pin "14") (pinfunction "SDO_14") (pintype "output"))
    )
    (net (code "69") (name "/SS") (class "Default")
      (node (ref "IC2") (pin "19") (pinfunction "PB0_(~{SS}/PCINT0)_19") (pintype "bidirectional"))
      (node (ref "P17") (pin "8") (pinfunction "8_8") (pintype "passive"))
      (node (ref "TEST-HEADER") (pin "1") (pinfunction "1_1") (pintype "passive"))
    )
    (net (code "70") (name "/STCK") (class "Default")
      (node (ref "P13") (pin "1") (pinfunction "1_1") (pintype "passive"))
      (node (ref "U15") (pin "17") (pinfunction "STCK_17") (pintype "input"))
    )
    (net (code "71") (name "/TX0") (class "Default")
      (node (ref "IC2") (pin "3") (pinfunction "PE1_(TXD0)_3") (pintype "bidirectional"))
      (node (ref "P14") (pin "7") (pinfunction "7_7") (pintype "passive"))
      (node (ref "Rp1") (pin "6") (pinfunction "6_6") (pintype "passive"))
    )
    (net (code "72") (name "/TX2") (class "Default")
      (node (ref "IC2") (pin "13") (pinfunction "PH1_(TXD2)_13") (pintype "bidirectional"))
      (node (ref "P16") (pin "7") (pinfunction "7_7") (pintype "passive"))
      (node (ref "P20") (pin "4") (pinfunction "4_4") (pintype "passive"))
      (node (ref "U11") (pin "17") (pinfunction "SHD/SD2_17") (pintype "bidirectional"))
    )
    (net (code "73") (name "/TX3") (class "Default")
      (node (ref "IC2") (pin "64") (pinfunction "PJ1_(TXD3/PCINT10)_64") (pintype "bidirectional"))
      (node (ref "P18") (pin "16") (pinfunction "16_16") (pintype "passive"))
      (node (ref "TEST-HEADER") (pin "2") (pinfunction "2_2") (pintype "passive"))
    )
    (net (code "74") (name "/TXD") (class "Default")
      (node (ref "CP2104") (pin "21") (pinfunction "TXD_21") (pintype "output"))
      (node (ref "EN1") (pin "1") (pinfunction "1_1") (pintype "passive"))
      (node (ref "Rp3") (pin "5") (pinfunction "5_5") (pintype "passive"))
      (node (ref "U14") (pin "4") (pinfunction "I/O_3_4") (pintype "passive"))
      (node (ref "UART") (pin "5") (pinfunction "5_5") (pintype "passive"))
    )
    (net (code "75") (name "/TXD0") (class "Default")
      (node (ref "EN2") (pin "2") (pinfunction "2_2") (pintype "passive"))
      (node (ref "P23") (pin "2") (pinfunction "2_2") (pintype "passive"))
      (node (ref "U11") (pin "35") (pinfunction "TXD0_35") (pintype "bidirectional"))
    )
    (net (code "76") (name "/TXL") (class "Default")
      (node (ref "IC4") (pin "11") (pinfunction "PD5_(XCK_AIN4/PCINT12)_11") (pintype "bidirectional"))
      (node (ref "TX1") (pin "K") (pinfunction "K_K") (pintype "passive"))
    )
    (net (code "77") (name "/UGND") (class "Default")
      (node (ref "C5") (pin "2") (pinfunction "2_2") (pintype "passive"))
      (node (ref "FB1") (pin "2") (pinfunction "2_2") (pintype "passive"))
      (node (ref "GROUND-EN1") (pin "1") (pinfunction "1_1") (pintype "passive"))
      (node (ref "IC4") (pin "28") (pinfunction "UGND_28") (pintype "power_in"))
      (node (ref "J1") (pin "5") (pinfunction "GND_5") (pintype "passive"))
    )
    (net (code "78") (name "/USBVCC") (class "Default")
      (node (ref "C1") (pin "2") (pinfunction "2_2") (pintype "passive"))
      (node (ref "F1") (pin "2") (pinfunction "2_2") (pintype "passive"))
      (node (ref "IC4") (pin "31") (pinfunction "UVCC_31") (pintype "power_in"))
      (node (ref "Q1") (pin "3") (pinfunction "D_3") (pintype "passive"))
    )
    (net (code "79") (name "/USHIELD") (class "Default")
      (node (ref "FB1") (pin "1") (pinfunction "1_1") (pintype "passive"))
      (node (ref "J1") (pin "10") (pinfunction "SHLD5_10") (pintype "passive"))
      (node (ref "J1") (pin "11") (pinfunction "SHLD6_11") (pintype "passive"))
      (node (ref "J1") (pin "6") (pinfunction "SHLD1_6") (pintype "passive"))
      (node (ref "J1") (pin "7") (pinfunction "SHLD2_7") (pintype "passive"))
      (node (ref "J1") (pin "8") (pinfunction "SHLD3_8") (pintype "passive"))
      (node (ref "J1") (pin "9") (pinfunction "SHLD4_9") (pintype "passive"))
      (node (ref "Z1") (pin "1") (pinfunction "1_1") (pintype "passive"))
      (node (ref "Z2") (pin "1") (pinfunction "1_1") (pintype "passive"))
    )
    (net (code "80") (name "/VBUS") (class "Default")
      (node (ref "F1") (pin "1") (pinfunction "1_1") (pintype "passive"))
      (node (ref "J1") (pin "1") (pinfunction "VBUS_1") (pintype "passive"))
      (node (ref "J2") (pin "A4") (pinfunction "VBUS_A4") (pintype "passive"))
      (node (ref "J2") (pin "A9") (pinfunction "VBUS_A9") (pintype "passive"))
      (node (ref "J2") (pin "B4") (pinfunction "VBUS_B4") (pintype "passive"))
      (node (ref "J2") (pin "B9") (pinfunction "VBUS_B9") (pintype "passive"))
      (node (ref "J3") (pin "1") (pinfunction "VBUS_1") (pintype "passive"))
      (node (ref "J4") (pin "A4") (pinfunction "VBUS_A4") (pintype "passive"))
      (node (ref "J4") (pin "A9") (pinfunction "VBUS_A9") (pintype "passive"))
      (node (ref "J4") (pin "B4") (pinfunction "VBUS_B4") (pintype "passive"))
      (node (ref "J4") (pin "B9") (pinfunction "VBUS_B9") (pintype "passive"))
      (node (ref "R15") (pin "2") (pinfunction "2_2") (pintype "passive"))
    )
    (net (code "81") (name "/VBUS3.3") (class "Default")
      (node (ref "CP2104") (pin "8") (pinfunction "VBUS_8") (pintype "input"))
      (node (ref "R15") (pin "1") (pinfunction "1_1") (pintype "passive"))
      (node (ref "R16") (pin "2") (pinfunction "2_2") (pintype "passive"))
    )
    (net (code "82") (name "/VIN") (class "Default")
      (node (ref "C2") (pin "1") (pinfunction "1_1") (pintype "passive"))
      (node (ref "C3") (pin "1") (pinfunction "1_1") (pintype "passive"))
      (node (ref "D1") (pin "2") (pinfunction "K_2") (pintype "passive"))
      (node (ref "IC1") (pin "3") (pinfunction "VIN_3") (pintype "power_in"))
      (node (ref "R4") (pin "2") (pinfunction "2_2") (pintype "passive"))
    )
    (net (code "83") (name "/VUCAP") (class "Default")
      (node (ref "C5") (pin "1") (pinfunction "1_1") (pintype "passive"))
      (node (ref "IC4") (pin "27") (pinfunction "UCAP_27") (pintype "power_in"))
    )
    (net (code "84") (name "/XTAL1") (class "Default")
      (node (ref "IC2") (pin "34") (pinfunction "XTAL1_34") (pintype "input"))
      (node (ref "R12") (pin "2") (pinfunction "2_2") (pintype "passive"))
      (node (ref "Y2") (pin "3") (pinfunction "C2_3") (pintype "passive"))
    )
    (net (code "85") (name "/XTAL2") (class "Default")
      (node (ref "IC2") (pin "33") (pinfunction "XTAL2_33") (pintype "output"))
      (node (ref "R12") (pin "1") (pinfunction "1_1") (pintype "passive"))
      (node (ref "Y2") (pin "1") (pinfunction "C1_1") (pintype "passive"))
    )
    (net (code "86") (name "GND") (class "Default")
      (node (ref "C-VCC") (pin "1") (pinfunction "1_1") (pintype "passive"))
      (node (ref "C-VCCREG") (pin "1") (pinfunction "1_1") (pintype "passive"))
      (node (ref "C-VDD") (pin "1") (pinfunction "1_1") (pintype "passive"))
      (node (ref "C-VREG") (pin "1") (pinfunction "1_1") (pintype "passive"))
      (node (ref "C-VREGPOL") (pin "2") (pinfunction "2_2") (pintype "passive"))
      (node (ref "C-VS") (pin "1") (pinfunction "1_1") (pintype "passive"))
      (node (ref "C-VSREG") (pin "2") (pinfunction "2_2") (pintype "passive"))
      (node (ref "C1") (pin "1") (pinfunction "1_1") (pintype "passive"))
      (node (ref "C10") (pin "1") (pinfunction "1_1") (pintype "passive"))
      (node (ref "C11") (pin "2") (pinfunction "2_2") (pintype "passive"))
      (node (ref "C12") (pin "2") (pinfunction "2_2") (pintype "passive"))
      (node (ref "C13") (pin "2") (pinfunction "2_2") (pintype "passive"))
      (node (ref "C14") (pin "1") (pinfunction "1_1") (pintype "passive"))
      (node (ref "C15") (pin "1") (pinfunction "1_1") (pintype "passive"))
      (node (ref "C16") (pin "2") (pinfunction "2_2") (pintype "passive"))
      (node (ref "C17") (pin "1") (pinfunction "1_1") (pintype "passive"))
      (node (ref "C19") (pin "2") (pinfunction "2_2") (pintype "passive"))
      (node (ref "C2") (pin "2") (pinfunction "2_2") (pintype "passive"))
      (node (ref "C20") (pin "2") (pinfunction "2_2") (pintype "passive"))
      (node (ref "C21") (pin "2") (pinfunction "2_2") (pintype "passive"))
      (node (ref "C22") (pin "2") (pinfunction "2_2") (pintype "passive"))
      (node (ref "C23") (pin "2") (pinfunction "2_2") (pintype "passive"))
      (node (ref "C24") (pin "2") (pinfunction "2_2") (pintype "passive"))
      (node (ref "C25") (pin "2") (pinfunction "2_2") (pintype "passive"))
      (node (ref "C26") (pin "2") (pinfunction "2_2") (pintype "passive"))
      (node (ref "C27") (pin "2") (pinfunction "2_2") (pintype "passive"))
      (node (ref "C28") (pin "1") (pinfunction "1_1") (pintype "passive"))
      (node (ref "C29") (pin "2") (pinfunction "2_2") (pintype "passive"))
      (node (ref "C3") (pin "2") (pinfunction "2_2") (pintype "passive"))
      (node (ref "C30") (pin "1") (pinfunction "1_1") (pintype "passive"))
      (node (ref "C31") (pin "2") (pinfunction "2_2") (pintype "passive"))
      (node (ref "C32") (pin "2") (pinfunction "2_2") (pintype "passive"))
      (node (ref "C33") (pin "1") (pinfunction "1_1") (pintype "passive"))
      (node (ref "C34") (pin "2") (pinfunction "2_2") (pintype "passive"))
      (node (ref "C35") (pin "2") (pinfunction "2_2") (pintype "passive"))
      (node (ref "C36") (pin "2") (pinfunction "2_2") (pintype "passive"))
      (node (ref "C37") (pin "2") (pinfunction "2_2") (pintype "passive"))
      (node (ref "C38") (pin "2") (pinfunction "2_2") (pintype "passive"))
      (node (ref "C39") (pin "2") (pinfunction "2_2") (pintype "passive"))
      (node (ref "C4") (pin "2") (pinfunction "2_2") (pintype "passive"))
      (node (ref "C40") (pin "2") (pinfunction "2_2") (pintype "passive"))
      (node (ref "C41") (pin "1") (pinfunction "1_1") (pintype "passive"))
      (node (ref "C42") (pin "1") (pinfunction "1_1") (pintype "passive"))
      (node (ref "C6") (pin "2") (pinfunction "2_2") (pintype "passive"))
      (node (ref "C7") (pin "2") (pinfunction "2_2") (pintype "passive"))
      (node (ref "C8") (pin "2") (pinfunction "2_2") (pintype "passive"))
      (node (ref "C9") (pin "2") (pinfunction "2_2") (pintype "passive"))
      (node (ref "CP2104") (pin "2") (pinfunction "GND_2") (pintype "power_in"))
      (node (ref "CP2104") (pin "25") (pinfunction "GND_25") (pintype "power_in"))
      (node (ref "CalibrationHeader") (pin "2") (pinfunction "2_2") (pintype "passive"))
      (node (ref "Camera") (pin "2") (pinfunction "2_2") (pintype "passive"))
      (node (ref "EEPROM") (pin "1") (pinfunction "A0_1") (pintype "input"))
      (node (ref "EEPROM") (pin "2") (pinfunction "A1_2") (pintype "input"))
      (node (ref "EEPROM") (pin "3") (pinfunction "A2_3") (pintype "input"))
      (node (ref "EEPROM") (pin "4") (pinfunction "VSS_4") (pintype "power_in"))
      (node (ref "GROUND-EN1") (pin "2") (pinfunction "2_2") (pintype "passive"))
      (node (ref "IC1") (pin "1") (pinfunction "GND_1") (pintype "power_in"))
      (node (ref "IC2") (pin "11") (pinfunction "GND_11") (pintype "power_in"))
      (node (ref "IC2") (pin "32") (pinfunction "GND_32") (pintype "power_in"))
      (node (ref "IC2") (pin "62") (pinfunction "GND_62") (pintype "power_in"))
      (node (ref "IC2") (pin "81") (pinfunction "GND_81") (pintype "power_in"))
      (node (ref "IC2") (pin "99") (pinfunction "GND_99") (pintype "power_in"))
      (node (ref "IC3") (pin "2") (pinfunction "GND_2") (pintype "power_in"))
      (node (ref "IC4") (pin "3") (pinfunction "GND_3") (pintype "power_in"))
      (node (ref "IC4") (pin "33") (pinfunction "DAP_33") (pintype "power_in"))
      (node (ref "ICSP1") (pin "6") (pinfunction "6_6") (pintype "passive"))
      (node (ref "ICSP2") (pin "6") (pinfunction "6_6") (pintype "passive"))
      (node (ref "J2") (pin "A1") (pinfunction "GND_A1") (pintype "passive"))
      (node (ref "J2") (pin "A12") (pinfunction "GND_A12") (pintype "passive"))
      (node (ref "J2") (pin "B1") (pinfunction "GND_B1") (pintype "passive"))
      (node (ref "J2") (pin "B12") (pinfunction "GND_B12") (pintype "passive"))
      (node (ref "J2") (pin "G1") (pinfunction "GND_G1") (pintype "passive"))
      (node (ref "J2") (pin "G2") (pinfunction "GND_G2") (pintype "passive"))
      (node (ref "J2") (pin "Shell") (pinfunction "Shield_Shell") (pintype "passive"))
      (node (ref "J3") (pin "10") (pinfunction "SHLD5_10") (pintype "passive"))
      (node (ref "J3") (pin "11") (pinfunction "SHLD6_11") (pintype "passive"))
      (node (ref "J3") (pin "5") (pinfunction "GND_5") (pintype "passive"))
      (node (ref "J3") (pin "6") (pinfunction "SHLD1_6") (pintype "passive"))
      (node (ref "J3") (pin "7") (pinfunction "SHLD2_7") (pintype "passive"))
      (node (ref "J3") (pin "8") (pinfunction "SHLD3_8") (pintype "passive"))
      (node (ref "J3") (pin "9") (pinfunction "SHLD4_9") (pintype "passive"))
      (node (ref "J4") (pin "A1") (pinfunction "GND_A1") (pintype "passive"))
      (node (ref "J4") (pin "A12") (pinfunction "GND_A12") (pintype "passive"))
      (node (ref "J4") (pin "B1") (pinfunction "GND_B1") (pintype "passive"))
      (node (ref "J4") (pin "B12") (pinfunction "GND_B12") (pintype "passive"))
      (node (ref "J4") (pin "G1") (pinfunction "GND_G1") (pintype "passive"))
      (node (ref "J4") (pin "G2") (pinfunction "GND_G2") (pintype "passive"))
      (node (ref "J4") (pin "Shell") (pinfunction "Shield_Shell") (pintype "passive"))
      (node (ref "L2") (pin "K") (pinfunction "K_K") (pintype "passive"))
      (node (ref "M1") (pin "10") (pinfunction "PGND2_10") (pintype "power_in"))
      (node (ref "M1") (pin "18") (pinfunction "GND_18") (pintype "power_in"))
      (node (ref "M1") (pin "3") (pinfunction "PGND1_3") (pintype "power_in"))
      (node (ref "M1") (pin "4") (pinfunction "PGND1_4") (pintype "power_in"))
      (node (ref "M1") (pin "9") (pinfunction "PGND2_9") (pintype "power_in"))
      (node (ref "M2") (pin "10") (pinfunction "PGND2_10") (pintype "power_in"))
      (node (ref "M2") (pin "18") (pinfunction "GND_18") (pintype "power_in"))
      (node (ref "M2") (pin "3") (pinfunction "PGND1_3") (pintype "power_in"))
      (node (ref "M2") (pin "4") (pinfunction "PGND1_4") (pintype "power_in"))
      (node (ref "M2") (pin "9") (pinfunction "PGND2_9") (pintype "power_in"))
      (node (ref "ON1") (pin "K") (pinfunction "K_K") (pintype "passive"))
      (node (ref "P1") (pin "1") (pinfunction "1_1") (pintype "passive"))
      (node (ref "P3") (pin "2") (pinfunction "2_2") (pintype "passive"))
      (node (ref "P3") (pin "MP1") (pinfunction "MP1_MP1") (pintype "passive"))
      (node (ref "P3") (pin "MP2") (pinfunction "MP2_MP2") (pintype "passive"))
      (node (ref "P4") (pin "2") (pinfunction "2_2") (pintype "passive"))
      (node (ref "P4") (pin "MP1") (pinfunction "MP1_MP1") (pintype "passive"))
      (node (ref "P4") (pin "MP2") (pinfunction "MP2_MP2") (pintype "passive"))
      (node (ref "P6") (pin "MP1") (pinfunction "MP1_MP1") (pintype "passive"))
      (node (ref "P6") (pin "MP2") (pinfunction "MP2_MP2") (pintype "passive"))
      (node (ref "POWER") (pin "1") (pinfunction "1_1") (pintype "passive"))
      (node (ref "POWER") (pin "3") (pinfunction "3_3") (pintype "passive"))
      (node (ref "POWER") (pin "5") (pinfunction "5_5") (pintype "passive"))
      (node (ref "R13") (pin "1") (pinfunction "1_1") (pintype "passive"))
      (node (ref "R16") (pin "1") (pinfunction "1_1") (pintype "passive"))
      (node (ref "R23") (pin "2") (pinfunction "2_2") (pintype "passive"))
      (node (ref "R5") (pin "1") (pinfunction "1_1") (pintype "passive"))
      (node (ref "RA") (pin "1") (pinfunction "1_1") (pintype "passive"))
      (node (ref "RESET1") (pin "1") (pinfunction "1_1") (pintype "passive"))
      (node (ref "RESET1") (pin "3") (pinfunction "3_3") (pintype "passive"))
      (node (ref "SW1") (pin "1") (pinfunction "1_1") (pintype "passive"))
      (node (ref "SW2") (pin "1") (pinfunction "1_1") (pintype "passive"))
      (node (ref "SW3") (pin "1") (pinfunction "1_1") (pintype "passive"))
      (node (ref "TEST-HEADER") (pin "6") (pinfunction "6_6") (pintype "passive"))
      (node (ref "TEST-HEADER1") (pin "6") (pinfunction "6_6") (pintype "passive"))
      (node (ref "U1") (pin "4") (pinfunction "V-_4") (pintype "power_in"))
      (node (ref "U10") (pin "3") (pinfunction "VSS_3") (pintype "power_in"))
      (node (ref "U11") (pin "1") (pinfunction "GND_1") (pintype "power_in"))
      (node (ref "U11") (pin "15") (pinfunction "GND_15") (pintype "power_in"))
      (node (ref "U11") (pin "38") (pinfunction "GND_38") (pintype "power_in"))
      (node (ref "U12") (pin "1") (pinfunction "GND_1") (pintype "power_in"))
      (node (ref "U12") (pin "11") (pinfunction "GND_11") (pintype "power_in"))
      (node (ref "U12") (pin "13") (pinfunction "GND_13") (pintype "power_in"))
      (node (ref "U12") (pin "22") (pinfunction "GND_22") (pintype "power_in"))
      (node (ref "U12") (pin "35") (pinfunction "GND_35") (pintype "power_in"))
      (node (ref "U13") (pin "2") (pinfunction "GND_2") (pintype "power_in"))
      (node (ref "U14") (pin "2") (pinfunction "GND_2") (pintype "power_in"))
      (node (ref "U15") (pin "100") (pinfunction "SENSEA_P_100") (pintype "passive"))
      (node (ref "U15") (pin "101") (pinfunction "SENSEB_P_101") (pintype "passive"))
      (node (ref "U15") (pin "102") (pinfunction "SENSEB_P_102") (pintype "passive"))
      (node (ref "U15") (pin "20") (pinfunction "SENSEA_S_20") (pintype "input"))
      (node (ref "U15") (pin "21") (pinfunction "GND_21") (pintype "power_in"))
      (node (ref "U15") (pin "34") (pinfunction "SENSEA_P_34") (pintype "passive"))
      (node (ref "U15") (pin "35") (pinfunction "SENSEA_P_35") (pintype "passive"))
      (node (ref "U15") (pin "36") (pinfunction "SENSEA_P_36") (pintype "passive"))
      (node (ref "U15") (pin "39") (pinfunction "SENSEA_P_39") (pintype "passive"))
      (node (ref "U15") (pin "40") (pinfunction "SENSEA_P_40") (pintype "passive"))
      (node (ref "U15") (pin "41") (pinfunction "SENSEA_P_41") (pintype "passive"))
      (node (ref "U15") (pin "59") (pinfunction "GND_59") (pintype "power_in"))
      (node (ref "U15") (pin "77") (pinfunction "SENSEB_P_77") (pintype "passive"))
      (node (ref "U15") (pin "78") (pinfunction "SENSEB_P_78") (pintype "passive"))
      (node (ref "U15") (pin "79") (pinfunction "SENSEB_P_79") (pintype "passive"))
      (node (ref "U15") (pin "8") (pinfunction "GND_8") (pintype "power_in"))
      (node (ref "U15") (pin "82") (pinfunction "SENSEB_P_82") (pintype "passive"))
      (node (ref "U15") (pin "83") (pinfunction "SENSEB_P_83") (pintype "passive"))
      (node (ref "U15") (pin "84") (pinfunction "SENSEB_P_84") (pintype "passive"))
      (node (ref "U15") (pin "9") (pinfunction "SENSEB_S_9") (pintype "input"))
      (node (ref "U15") (pin "98") (pinfunction "GND_98") (pintype "power_in"))
      (node (ref "U15") (pin "99") (pinfunction "SENSEA_P_99") (pintype "passive"))
      (node (ref "U2") (pin "3") (pinfunction "VSS_3") (pintype "power_in"))
      (node (ref "U3") (pin "3") (pinfunction "VSS_3") (pintype "power_in"))
      (node (ref "U4") (pin "3") (pinfunction "VSS_3") (pintype "power_in"))
      (node (ref "U5") (pin "3") (pinfunction "VSS_3") (pintype "power_in"))
      (node (ref "U6") (pin "3") (pinfunction "VSS_3") (pintype "power_in"))
      (node (ref "U7") (pin "3") (pinfunction "VSS_3") (pintype "power_in"))
      (node (ref "U8") (pin "3") (pinfunction "VSS_3") (pintype "power_in"))
      (node (ref "U9") (pin "3") (pinfunction "VSS_3") (pintype "power_in"))
      (node (ref "UART") (pin "2") (pinfunction "2_2") (pintype "passive"))
      (node (ref "X1") (pin "1") (pinfunction "1_1") (pintype "passive"))
      (node (ref "Y2") (pin "2") (pinfunction "GND_2") (pintype "power_in"))
    )
    (net (code "87") (name "Net-(CP2104-VPP)") (class "Default")
      (node (ref "C33") (pin "2") (pinfunction "2_2") (pintype "passive"))
      (node (ref "CP2104") (pin "16") (pinfunction "VPP_16") (pintype "passive"))
    )
    (net (code "88") (name "Net-(CP2104-~{RST})") (class "Default")
      (node (ref "CP2104") (pin "9") (pinfunction "~{RST}_9") (pintype "bidirectional"))
      (node (ref "R17") (pin "1") (pinfunction "1_1") (pintype "passive"))
    )
    (net (code "89") (name "Net-(D4-PadK)") (class "Default")
      (node (ref "D4") (pin "K") (pinfunction "K_K") (pintype "passive"))
      (node (ref "Rp3") (pin "1") (pinfunction "1_1") (pintype "passive"))
    )
    (net (code "90") (name "Net-(D5-PadK)") (class "Default")
      (node (ref "D5") (pin "K") (pinfunction "K_K") (pintype "passive"))
      (node (ref "Rp3") (pin "2") (pinfunction "2_2") (pintype "passive"))
    )
    (net (code "91") (name "Net-(D6-PadK)") (class "Default")
      (node (ref "D6") (pin "K") (pinfunction "K_K") (pintype "passive"))
      (node (ref "Rp3") (pin "3") (pinfunction "3_3") (pintype "passive"))
    )
    (net (code "92") (name "Net-(D7-PadK)") (class "Default")
      (node (ref "D7") (pin "K") (pinfunction "K_K") (pintype "passive"))
      (node (ref "Rp3") (pin "4") (pinfunction "4_4") (pintype "passive"))
    )
    (net (code "93") (name "Net-(D8-K)") (class "Default")
      (node (ref "C-FLY") (pin "1") (pinfunction "1_1") (pintype "passive"))
      (node (ref "D8") (pin "2") (pinfunction "K_2") (pintype "passive"))
      (node (ref "D9") (pin "1") (pinfunction "A_1") (pintype "passive"))
    )
    (net (code "94") (name "Net-(D9-K)") (class "Default")
      (node (ref "C-BOOT") (pin "2") (pinfunction "2_2") (pintype "passive"))
      (node (ref "D9") (pin "2") (pinfunction "K_2") (pintype "passive"))
      (node (ref "U15") (pin "56") (pinfunction "VBOOT_56") (pintype "power_in"))
    )
    (net (code "95") (name "Net-(EEPROM-WP)") (class "Default")
      (node (ref "EEPROM") (pin "7") (pinfunction "WP_7") (pintype "input"))
      (node (ref "R24") (pin "1") (pinfunction "1_1") (pintype "passive"))
    )
    (net (code "96") (name "Net-(IC2-PB4_(OC2A{slash}PCINT4))") (class "Default")
      (node (ref "IC2") (pin "23") (pinfunction "PB4_(OC2A/PCINT4)_23") (pintype "bidirectional"))
      (node (ref "P17") (pin "4") (pinfunction "4_4") (pintype "passive"))
    )
    (net (code "97") (name "Net-(IC2-PB5_(OC1A{slash}PCINT5))") (class "Default")
      (node (ref "IC2") (pin "24") (pinfunction "PB5_(OC1A/PCINT5)_24") (pintype "bidirectional"))
      (node (ref "P17") (pin "3") (pinfunction "3_3") (pintype "passive"))
    )
    (net (code "98") (name "Net-(IC2-PB6_(OC1B{slash}PCINT6))") (class "Default")
      (node (ref "IC2") (pin "25") (pinfunction "PB6_(OC1B/PCINT6)_25") (pintype "bidirectional"))
      (node (ref "P17") (pin "2") (pinfunction "2_2") (pintype "passive"))
    )
    (net (code "99") (name "Net-(IC2-PC0_(A8))") (class "Default")
      (node (ref "IC2") (pin "53") (pinfunction "PC0_(A8)_53") (pintype "bidirectional"))
      (node (ref "P22") (pin "8") (pinfunction "8_8") (pintype "passive"))
    )
    (net (code "100") (name "Net-(IC2-PC1_(A9))") (class "Default")
      (node (ref "IC2") (pin "54") (pinfunction "PC1_(A9)_54") (pintype "bidirectional"))
      (node (ref "P22") (pin "7") (pinfunction "7_7") (pintype "passive"))
    )
    (net (code "101") (name "Net-(IC2-PC2_(A10))") (class "Default")
      (node (ref "IC2") (pin "55") (pinfunction "PC2_(A10)_55") (pintype "bidirectional"))
      (node (ref "P22") (pin "6") (pinfunction "6_6") (pintype "passive"))
    )
    (net (code "102") (name "Net-(IC2-PC3_(A11))") (class "Default")
      (node (ref "IC2") (pin "56") (pinfunction "PC3_(A11)_56") (pintype "bidirectional"))
      (node (ref "P22") (pin "5") (pinfunction "5_5") (pintype "passive"))
    )
    (net (code "103") (name "Net-(IC2-PC4_(A12))") (class "Default")
      (node (ref "IC2") (pin "57") (pinfunction "PC4_(A12)_57") (pintype "bidirectional"))
      (node (ref "P22") (pin "4") (pinfunction "4_4") (pintype "passive"))
    )
    (net (code "104") (name "Net-(IC2-PC5_(A13))") (class "Default")
      (node (ref "IC2") (pin "58") (pinfunction "PC5_(A13)_58") (pintype "bidirectional"))
      (node (ref "P22") (pin "3") (pinfunction "3_3") (pintype "passive"))
    )
    (net (code "105") (name "Net-(IC2-PC6_(A14))") (class "Default")
      (node (ref "IC2") (pin "59") (pinfunction "PC6_(A14)_59") (pintype "bidirectional"))
      (node (ref "P22") (pin "2") (pinfunction "2_2") (pintype "passive"))
    )
    (net (code "106") (name "Net-(IC2-PC7_(A15))") (class "Default")
      (node (ref "IC2") (pin "60") (pinfunction "PC7_(A15)_60") (pintype "bidirectional"))
      (node (ref "P22") (pin "1") (pinfunction "1_1") (pintype "passive"))
    )
    (net (code "107") (name "Net-(IC2-PD4_(ICP1))") (class "Default")
      (node (ref "IC2") (pin "47") (pinfunction "PD4_(ICP1)_47") (pintype "bidirectional"))
      (node (ref "P21") (pin "4") (pinfunction "4_4") (pintype "passive"))
    )
    (net (code "108") (name "Net-(IC2-PD5_(XCK1))") (class "Default")
      (node (ref "IC2") (pin "48") (pinfunction "PD5_(XCK1)_48") (pintype "bidirectional"))
      (node (ref "P21") (pin "3") (pinfunction "3_3") (pintype "passive"))
    )
    (net (code "109") (name "Net-(IC2-PD6_(T1))") (class "Default")
      (node (ref "IC2") (pin "49") (pinfunction "PD6_(T1)_49") (pintype "bidirectional"))
      (node (ref "P21") (pin "2") (pinfunction "2_2") (pintype "passive"))
    )
    (net (code "110") (name "Net-(IC2-PD7_(T0))") (class "Default")
      (node (ref "IC2") (pin "50") (pinfunction "PD7_(T0)_50") (pintype "bidirectional"))
      (node (ref "P21") (pin "1") (pinfunction "1_1") (pintype "passive"))
    )
    (net (code "111") (name "Net-(IC2-PE2_(XCK0{slash}AIN0))") (class "Default")
      (node (ref "IC2") (pin "4") (pinfunction "PE2_(XCK0/AIN0)_4") (pintype "bidirectional"))
      (node (ref "P14") (pin "6") (pinfunction "6_6") (pintype "passive"))
    )
    (net (code "112") (name "Net-(IC2-PE3_(OC3A{slash}AIN1))") (class "Default")
      (node (ref "IC2") (pin "5") (pinfunction "PE3_(OC3A/AIN1)_5") (pintype "bidirectional"))
      (node (ref "P14") (pin "5") (pinfunction "5_5") (pintype "passive"))
    )
    (net (code "113") (name "Net-(IC2-PE4_(OC3B{slash}INT4))") (class "Default")
      (node (ref "IC2") (pin "6") (pinfunction "PE4_(OC3B/INT4)_6") (pintype "bidirectional"))
      (node (ref "P14") (pin "4") (pinfunction "4_4") (pintype "passive"))
    )
    (net (code "114") (name "Net-(IC2-PE6_(T3{slash}INT6))") (class "Default")
      (node (ref "IC2") (pin "8") (pinfunction "PE6_(T3/INT6)_8") (pintype "bidirectional"))
      (node (ref "P14") (pin "2") (pinfunction "2_2") (pintype "passive"))
    )
    (net (code "115") (name "Net-(IC2-PE7_(CLKO{slash}ICP3{slash}INT7))") (class "Default")
      (node (ref "IC2") (pin "9") (pinfunction "PE7_(CLKO/ICP3/INT7)_9") (pintype "bidirectional"))
      (node (ref "P14") (pin "1") (pinfunction "1_1") (pintype "passive"))
    )
    (net (code "116") (name "Net-(IC2-PF0_(ADC0))") (class "Default")
      (node (ref "IC2") (pin "97") (pinfunction "PF0_(ADC0)_97") (pintype "bidirectional"))
      (node (ref "P15") (pin "1") (pinfunction "1_1") (pintype "passive"))
    )
    (net (code "117") (name "Net-(IC2-PF1_(ADC1))") (class "Default")
      (node (ref "IC2") (pin "96") (pinfunction "PF1_(ADC1)_96") (pintype "bidirectional"))
      (node (ref "P15") (pin "2") (pinfunction "2_2") (pintype "passive"))
    )
    (net (code "118") (name "Net-(IC2-PF2_(ADC2))") (class "Default")
      (node (ref "IC2") (pin "95") (pinfunction "PF2_(ADC2)_95") (pintype "bidirectional"))
      (node (ref "P15") (pin "3") (pinfunction "3_3") (pintype "passive"))
    )
    (net (code "119") (name "Net-(IC2-PF3_(ADC3))") (class "Default")
      (node (ref "IC2") (pin "94") (pinfunction "PF3_(ADC3)_94") (pintype "bidirectional"))
      (node (ref "P15") (pin "4") (pinfunction "4_4") (pintype "passive"))
    )
    (net (code "120") (name "Net-(IC2-PF4_(ADC4{slash}TCK))") (class "Default")
      (node (ref "IC2") (pin "93") (pinfunction "PF4_(ADC4/TCK)_93") (pintype "bidirectional"))
      (node (ref "P15") (pin "5") (pinfunction "5_5") (pintype "passive"))
    )
    (net (code "121") (name "Net-(IC2-PF5_(ADC5{slash}TMS))") (class "Default")
      (node (ref "IC2") (pin "92") (pinfunction "PF5_(ADC5/TMS)_92") (pintype "bidirectional"))
      (node (ref "P15") (pin "6") (pinfunction "6_6") (pintype "passive"))
    )
    (net (code "122") (name "Net-(IC2-PF6_(ADC6{slash}TDO))") (class "Default")
      (node (ref "IC2") (pin "91") (pinfunction "PF6_(ADC6/TDO)_91") (pintype "bidirectional"))
      (node (ref "P15") (pin "7") (pinfunction "7_7") (pintype "passive"))
    )
    (net (code "123") (name "Net-(IC2-PF7_(ADC7{slash}TDI))") (class "Default")
      (node (ref "IC2") (pin "90") (pinfunction "PF7_(ADC7/TDI)_90") (pintype "bidirectional"))
      (node (ref "P15") (pin "8") (pinfunction "8_8") (pintype "passive"))
    )
    (net (code "124") (name "Net-(IC2-PG0_(WR))") (class "Default")
      (node (ref "IC2") (pin "51") (pinfunction "PG0_(WR)_51") (pintype "bidirectional"))
      (node (ref "P24") (pin "1") (pinfunction "1_1") (pintype "passive"))
    )
    (net (code "125") (name "Net-(IC2-PG1_(RD))") (class "Default")
      (node (ref "IC2") (pin "52") (pinfunction "PG1_(RD)_52") (pintype "bidirectional"))
      (node (ref "P24") (pin "2") (pinfunction "2_2") (pintype "passive"))
    )
    (net (code "126") (name "Net-(IC2-PG3_(TOSC2))") (class "Default")
      (node (ref "IC2") (pin "28") (pinfunction "PG3_(TOSC2)_28") (pintype "bidirectional"))
      (node (ref "P24") (pin "4") (pinfunction "4_4") (pintype "passive"))
    )
    (net (code "127") (name "Net-(IC2-PG4_(TOSC1))") (class "Default")
      (node (ref "IC2") (pin "29") (pinfunction "PG4_(TOSC1)_29") (pintype "bidirectional"))
      (node (ref "P24") (pin "5") (pinfunction "5_5") (pintype "passive"))
    )
    (net (code "128") (name "Net-(IC2-PG5_(OC0B))") (class "Default")
      (node (ref "IC2") (pin "1") (pinfunction "PG5_(OC0B)_1") (pintype "bidirectional"))
      (node (ref "P24") (pin "6") (pinfunction "6_6") (pintype "passive"))
    )
    (net (code "129") (name "Net-(IC2-PH2_(XCK2))") (class "Default")
      (node (ref "IC2") (pin "14") (pinfunction "PH2_(XCK2)_14") (pintype "bidirectional"))
      (node (ref "P16") (pin "6") (pinfunction "6_6") (pintype "passive"))
    )
    (net (code "130") (name "Net-(IC2-PH7_(T4))") (class "Default")
      (node (ref "IC2") (pin "27") (pinfunction "PH7_(T4)_27") (pintype "bidirectional"))
      (node (ref "P16") (pin "1") (pinfunction "1_1") (pintype "passive"))
    )
    (net (code "131") (name "Net-(IC2-PJ2_(XCK3{slash}PCINT11))") (class "Default")
      (node (ref "IC2") (pin "65") (pinfunction "PJ2_(XCK3/PCINT11)_65") (pintype "bidirectional"))
      (node (ref "P18") (pin "15") (pinfunction "15_15") (pintype "passive"))
    )
    (net (code "132") (name "Net-(IC2-PJ3_(PCINT12))") (class "Default")
      (node (ref "IC2") (pin "66") (pinfunction "PJ3_(PCINT12)_66") (pintype "bidirectional"))
      (node (ref "P18") (pin "14") (pinfunction "14_14") (pintype "passive"))
    )
    (net (code "133") (name "Net-(IC2-PJ4_(PCINT13))") (class "Default")
      (node (ref "IC2") (pin "67") (pinfunction "PJ4_(PCINT13)_67") (pintype "bidirectional"))
      (node (ref "P18") (pin "13") (pinfunction "13_13") (pintype "passive"))
    )
    (net (code "134") (name "Net-(IC2-PJ5_(PCINT14))") (class "Default")
      (node (ref "IC2") (pin "68") (pinfunction "PJ5_(PCINT14)_68") (pintype "bidirectional"))
      (node (ref "P18") (pin "12") (pinfunction "12_12") (pintype "passive"))
    )
    (net (code "135") (name "Net-(IC2-PJ6_(PCINT15))") (class "Default")
      (node (ref "IC2") (pin "69") (pinfunction "PJ6_(PCINT15)_69") (pintype "bidirectional"))
      (node (ref "P18") (pin "11") (pinfunction "11_11") (pintype "passive"))
    )
    (net (code "136") (name "Net-(IC2-PJ7)") (class "Default")
      (node (ref "IC2") (pin "79") (pinfunction "PJ7_79") (pintype "bidirectional"))
      (node (ref "P18") (pin "10") (pinfunction "10_10") (pintype "passive"))
    )
    (net (code "137") (name "Net-(IC2-PK0_(ADC8{slash}PCINT16))") (class "Default")
      (node (ref "IC2") (pin "89") (pinfunction "PK0_(ADC8/PCINT16)_89") (pintype "bidirectional"))
      (node (ref "P15") (pin "10") (pinfunction "10_10") (pintype "passive"))
    )
    (net (code "138") (name "Net-(IC2-PK1_(ADC9{slash}PCINT17))") (class "Default")
      (node (ref "IC2") (pin "88") (pinfunction "PK1_(ADC9/PCINT17)_88") (pintype "bidirectional"))
      (node (ref "P15") (pin "11") (pinfunction "11_11") (pintype "passive"))
    )
    (net (code "139") (name "Net-(IC2-PK2_(ADC10{slash}PCINT18))") (class "Default")
      (node (ref "IC2") (pin "87") (pinfunction "PK2_(ADC10/PCINT18)_87") (pintype "bidirectional"))
      (node (ref "P15") (pin "12") (pinfunction "12_12") (pintype "passive"))
    )
    (net (code "140") (name "Net-(IC2-PK3_(ADC11{slash}PCINT19))") (class "Default")
      (node (ref "IC2") (pin "86") (pinfunction "PK3_(ADC11/PCINT19)_86") (pintype "bidirectional"))
      (node (ref "P15") (pin "13") (pinfunction "13_13") (pintype "passive"))
    )
    (net (code "141") (name "Net-(IC2-PK4_(ADC12{slash}PCINT20))") (class "Default")
      (node (ref "IC2") (pin "85") (pinfunction "PK4_(ADC12/PCINT20)_85") (pintype "bidirectional"))
      (node (ref "P15") (pin "14") (pinfunction "14_14") (pintype "passive"))
    )
    (net (code "142") (name "Net-(IC2-PK5_(ADC13{slash}PCINT21))") (class "Default")
      (node (ref "IC2") (pin "84") (pinfunction "PK5_(ADC13/PCINT21)_84") (pintype "bidirectional"))
      (node (ref "P15") (pin "15") (pinfunction "15_15") (pintype "passive"))
    )
    (net (code "143") (name "Net-(IC2-PK6_(ADC14{slash}PCINT22))") (class "Default")
      (node (ref "IC2") (pin "83") (pinfunction "PK6_(ADC14/PCINT22)_83") (pintype "bidirectional"))
      (node (ref "P15") (pin "16") (pinfunction "16_16") (pintype "passive"))
    )
    (net (code "144") (name "Net-(IC2-PK7_(ADC15{slash}PCINT23))") (class "Default")
      (node (ref "IC2") (pin "82") (pinfunction "PK7_(ADC15/PCINT23)_82") (pintype "bidirectional"))
      (node (ref "P15") (pin "17") (pinfunction "17_17") (pintype "passive"))
    )
    (net (code "145") (name "Net-(IC2-PL0_(ICP4))") (class "Default")
      (node (ref "IC2") (pin "35") (pinfunction "PL0_(ICP4)_35") (pintype "bidirectional"))
      (node (ref "P19") (pin "8") (pinfunction "8_8") (pintype "passive"))
    )
    (net (code "146") (name "Net-(IC2-PL1_(ICP5))") (class "Default")
      (node (ref "IC2") (pin "36") (pinfunction "PL1_(ICP5)_36") (pintype "bidirectional"))
      (node (ref "P19") (pin "7") (pinfunction "7_7") (pintype "passive"))
    )
    (net (code "147") (name "Net-(IC2-PL2_(T5))") (class "Default")
      (node (ref "IC2") (pin "37") (pinfunction "PL2_(T5)_37") (pintype "bidirectional"))
      (node (ref "P19") (pin "6") (pinfunction "6_6") (pintype "passive"))
    )
    (net (code "148") (name "Net-(IC2-PL3_(OC5A))") (class "Default")
      (node (ref "IC2") (pin "38") (pinfunction "PL3_(OC5A)_38") (pintype "bidirectional"))
      (node (ref "P19") (pin "5") (pinfunction "5_5") (pintype "passive"))
    )
    (net (code "149") (name "Net-(IC2-PL4_(OC5B))") (class "Default")
      (node (ref "IC2") (pin "39") (pinfunction "PL4_(OC5B)_39") (pintype "bidirectional"))
      (node (ref "P19") (pin "4") (pinfunction "4_4") (pintype "passive"))
    )
    (net (code "150") (name "Net-(IC2-PL5_(OC5C))") (class "Default")
      (node (ref "IC2") (pin "40") (pinfunction "PL5_(OC5C)_40") (pintype "bidirectional"))
      (node (ref "P19") (pin "3") (pinfunction "3_3") (pintype "passive"))
    )
    (net (code "151") (name "Net-(IC2-PL6)") (class "Default")
      (node (ref "IC2") (pin "41") (pinfunction "PL6_41") (pintype "bidirectional"))
      (node (ref "P19") (pin "2") (pinfunction "2_2") (pintype "passive"))
    )
    (net (code "152") (name "Net-(IC2-PL7)") (class "Default")
      (node (ref "IC2") (pin "42") (pinfunction "PL7_42") (pintype "bidirectional"))
      (node (ref "P19") (pin "1") (pinfunction "1_1") (pintype "passive"))
    )
    (net (code "153") (name "Net-(JTAG-Pad1)") (class "Default")
      (node (ref "JTAG") (pin "1") (pinfunction "1_1") (pintype "passive"))
      (node (ref "Rp2") (pin "1") (pinfunction "1_1") (pintype "passive"))
    )
    (net (code "154") (name "Net-(JTAG-Pad2)") (class "Default")
      (node (ref "JTAG") (pin "2") (pinfunction "2_2") (pintype "passive"))
      (node (ref "Rp2") (pin "2") (pinfunction "2_2") (pintype "passive"))
    )
    (net (code "155") (name "Net-(JTAG-Pad3)") (class "Default")
      (node (ref "JTAG") (pin "3") (pinfunction "3_3") (pintype "passive"))
      (node (ref "Rp2") (pin "3") (pinfunction "3_3") (pintype "passive"))
    )
    (net (code "156") (name "Net-(JTAG-Pad4)") (class "Default")
      (node (ref "JTAG") (pin "4") (pinfunction "4_4") (pintype "passive"))
      (node (ref "Rp2") (pin "4") (pinfunction "4_4") (pintype "passive"))
    )
    (net (code "157") (name "Net-(L2-PadA)") (class "Default")
      (node (ref "L2") (pin "A") (pinfunction "A_A") (pintype "passive"))
      (node (ref "R6") (pin "2") (pinfunction "2_2") (pintype "passive"))
    )
    (net (code "158") (name "Net-(M1-AO1-Pad1)") (class "Default")
      (node (ref "M1") (pin "1") (pinfunction "AO1_1") (pintype "tri_state"))
      (node (ref "M1") (pin "2") (pinfunction "AO1_2") (pintype "tri_state"))
      (node (ref "P8") (pin "1") (pinfunction "1_1") (pintype "passive"))
    )
    (net (code "159") (name "Net-(M1-AO2-Pad5)") (class "Default")
      (node (ref "M1") (pin "5") (pinfunction "AO2_5") (pintype "tri_state"))
      (node (ref "M1") (pin "6") (pinfunction "AO2_6") (pintype "tri_state"))
      (node (ref "P8") (pin "2") (pinfunction "2_2") (pintype "passive"))
    )
    (net (code "160") (name "Net-(M1-BO1-Pad11)") (class "Default")
      (node (ref "M1") (pin "11") (pinfunction "BO1_11") (pintype "tri_state"))
      (node (ref "M1") (pin "12") (pinfunction "BO1_12") (pintype "tri_state"))
      (node (ref "P10") (pin "1") (pinfunction "1_1") (pintype "passive"))
    )
    (net (code "161") (name "Net-(M1-BO2-Pad7)") (class "Default")
      (node (ref "M1") (pin "7") (pinfunction "BO2_7") (pintype "tri_state"))
      (node (ref "M1") (pin "8") (pinfunction "BO2_8") (pintype "tri_state"))
      (node (ref "P10") (pin "2") (pinfunction "2_2") (pintype "passive"))
    )
    (net (code "162") (name "Net-(M2-AO1-Pad1)") (class "Default")
      (node (ref "M2") (pin "1") (pinfunction "AO1_1") (pintype "tri_state"))
      (node (ref "M2") (pin "2") (pinfunction "AO1_2") (pintype "tri_state"))
      (node (ref "P9") (pin "1") (pinfunction "1_1") (pintype "passive"))
    )
    (net (code "163") (name "Net-(M2-AO2-Pad5)") (class "Default")
      (node (ref "M2") (pin "5") (pinfunction "AO2_5") (pintype "tri_state"))
      (node (ref "M2") (pin "6") (pinfunction "AO2_6") (pintype "tri_state"))
      (node (ref "P9") (pin "2") (pinfunction "2_2") (pintype "passive"))
    )
    (net (code "164") (name "Net-(M2-BO1-Pad11)") (class "Default")
      (node (ref "M2") (pin "11") (pinfunction "BO1_11") (pintype "tri_state"))
      (node (ref "M2") (pin "12") (pinfunction "BO1_12") (pintype "tri_state"))
      (node (ref "P11") (pin "1") (pinfunction "1_1") (pintype "passive"))
    )
    (net (code "165") (name "Net-(M2-BO2-Pad7)") (class "Default")
      (node (ref "M2") (pin "7") (pinfunction "BO2_7") (pintype "tri_state"))
      (node (ref "M2") (pin "8") (pinfunction "BO2_8") (pintype "tri_state"))
      (node (ref "P11") (pin "2") (pinfunction "2_2") (pintype "passive"))
    )
    (net (code "166") (name "Net-(ON1-PadA)") (class "Default")
      (node (ref "ON1") (pin "A") (pinfunction "A_A") (pintype "passive"))
      (node (ref "R3") (pin "2") (pinfunction "2_2") (pintype "passive"))
    )
    (net (code "167") (name "Net-(P12-Pad1)") (class "Default")
      (node (ref "P12") (pin "1") (pinfunction "1_1") (pintype "passive"))
      (node (ref "P6") (pin "1") (pinfunction "1_1") (pintype "passive"))
      (node (ref "U15") (pin "38") (pinfunction "OUTA1_38") (pintype "output"))
      (node (ref "U15") (pin "42") (pinfunction "OUTA1_42") (pintype "output"))
      (node (ref "U15") (pin "53") (pinfunction "OUTA1_53") (pintype "output"))
      (node (ref "U15") (pin "93") (pinfunction "OUTA1_93") (pintype "output"))
    )
    (net (code "168") (name "Net-(P12-Pad2)") (class "Default")
      (node (ref "P12") (pin "2") (pinfunction "2_2") (pintype "passive"))
      (node (ref "P6") (pin "2") (pinfunction "2_2") (pintype "passive"))
      (node (ref "U15") (pin "65") (pinfunction "OUTB1_65") (pintype "output"))
      (node (ref "U15") (pin "76") (pinfunction "OUTB1_76") (pintype "output"))
      (node (ref "U15") (pin "80") (pinfunction "OUTB1_80") (pintype "output"))
      (node (ref "U15") (pin "96") (pinfunction "OUTB1_96") (pintype "output"))
    )
    (net (code "169") (name "Net-(P12-Pad3)") (class "Default")
      (node (ref "P12") (pin "3") (pinfunction "3_3") (pintype "passive"))
      (node (ref "P6") (pin "3") (pinfunction "3_3") (pintype "passive"))
      (node (ref "U15") (pin "22") (pinfunction "OUTA2_22") (pintype "output"))
      (node (ref "U15") (pin "33") (pinfunction "OUTA2_33") (pintype "output"))
      (node (ref "U15") (pin "37") (pinfunction "OUTA2_37") (pintype "output"))
      (node (ref "U15") (pin "92") (pinfunction "OUTA2_92") (pintype "output"))
    )
    (net (code "170") (name "Net-(P12-Pad4)") (class "Default")
      (node (ref "P12") (pin "4") (pinfunction "4_4") (pintype "passive"))
      (node (ref "P6") (pin "4") (pinfunction "4_4") (pintype "passive"))
      (node (ref "U15") (pin "7") (pinfunction "OUTB2_7") (pintype "output"))
      (node (ref "U15") (pin "81") (pinfunction "OUTB2_81") (pintype "output"))
      (node (ref "U15") (pin "85") (pinfunction "OUTB2_85") (pintype "output"))
      (node (ref "U15") (pin "97") (pinfunction "OUTB2_97") (pintype "output"))
    )
    (net (code "171") (name "Net-(Q2-B)") (class "Default")
      (node (ref "Q2") (pin "1") (pinfunction "B_1") (pintype "passive"))
      (node (ref "R18") (pin "2") (pinfunction "2_2") (pintype "passive"))
    )
    (net (code "172") (name "Net-(Q3-B)") (class "Default")
      (node (ref "Q3") (pin "1") (pinfunction "B_1") (pintype "passive"))
      (node (ref "R19") (pin "2") (pinfunction "2_2") (pintype "passive"))
    )
    (net (code "173") (name "Net-(RX1-PadA)") (class "Default")
      (node (ref "RX1") (pin "A") (pinfunction "A_A") (pintype "passive"))
      (node (ref "Rp1") (pin "8") (pinfunction "8_8") (pintype "passive"))
    )
    (net (code "174") (name "Net-(Rp1-Pad7)") (class "Default")
      (node (ref "Rp1") (pin "7") (pinfunction "7_7") (pintype "passive"))
      (node (ref "TX1") (pin "A") (pinfunction "A_A") (pintype "passive"))
    )
    (net (code "175") (name "Net-(U1A-IN-)") (class "Default")
      (node (ref "R6") (pin "1") (pinfunction "1_1") (pintype "passive"))
      (node (ref "U1") (pin "1") (pinfunction "OUT_1") (pintype "output"))
      (node (ref "U1") (pin "2") (pinfunction "IN-_2") (pintype "input"))
    )
    (net (code "176") (name "Net-(U2-DOUT)") (class "Default")
      (node (ref "U2") (pin "2") (pinfunction "DOUT_2") (pintype "output"))
      (node (ref "U3") (pin "4") (pinfunction "DIN_4") (pintype "input"))
    )
    (net (code "177") (name "Net-(U3-DOUT)") (class "Default")
      (node (ref "U3") (pin "2") (pinfunction "DOUT_2") (pintype "output"))
      (node (ref "U4") (pin "4") (pinfunction "DIN_4") (pintype "input"))
    )
    (net (code "178") (name "Net-(U4-DOUT)") (class "Default")
      (node (ref "U4") (pin "2") (pinfunction "DOUT_2") (pintype "output"))
      (node (ref "U5") (pin "4") (pinfunction "DIN_4") (pintype "input"))
    )
    (net (code "179") (name "Net-(U5-DOUT)") (class "Default")
      (node (ref "U5") (pin "2") (pinfunction "DOUT_2") (pintype "output"))
      (node (ref "U6") (pin "4") (pinfunction "DIN_4") (pintype "input"))
    )
    (net (code "180") (name "Net-(U6-DOUT)") (class "Default")
      (node (ref "U6") (pin "2") (pinfunction "DOUT_2") (pintype "output"))
      (node (ref "U7") (pin "4") (pinfunction "DIN_4") (pintype "input"))
    )
    (net (code "181") (name "Net-(U7-DOUT)") (class "Default")
      (node (ref "U7") (pin "2") (pinfunction "DOUT_2") (pintype "output"))
      (node (ref "U8") (pin "4") (pinfunction "DIN_4") (pintype "input"))
    )
    (net (code "182") (name "Net-(U8-DOUT)") (class "Default")
      (node (ref "U8") (pin "2") (pinfunction "DOUT_2") (pintype "output"))
      (node (ref "U9") (pin "4") (pinfunction "DIN_4") (pintype "input"))
    )
    (net (code "183") (name "Net-(U10-DIN)") (class "Default")
      (node (ref "U10") (pin "4") (pinfunction "DIN_4") (pintype "input"))
      (node (ref "U9") (pin "2") (pinfunction "DOUT_2") (pintype "output"))
    )
    (net (code "184") (name "Net-(U11-IO2)") (class "Default")
      (node (ref "PIN-OUT") (pin "21") (pinfunction "21_21") (pintype "passive"))
      (node (ref "U11") (pin "24") (pinfunction "IO2_24") (pintype "bidirectional"))
    )
    (net (code "185") (name "Net-(U11-IO4)") (class "Default")
      (node (ref "PIN-OUT") (pin "20") (pinfunction "20_20") (pintype "passive"))
      (node (ref "U11") (pin "26") (pinfunction "IO4_26") (pintype "bidirectional"))
    )
    (net (code "186") (name "Net-(U11-IO5)") (class "Default")
      (node (ref "PIN-OUT") (pin "19") (pinfunction "19_19") (pintype "passive"))
      (node (ref "U11") (pin "29") (pinfunction "IO5_29") (pintype "bidirectional"))
    )
    (net (code "187") (name "Net-(U11-IO16)") (class "Default")
      (node (ref "PIN-OUT") (pin "14") (pinfunction "14_14") (pintype "passive"))
      (node (ref "U11") (pin "27") (pinfunction "IO16_27") (pintype "bidirectional"))
    )
    (net (code "188") (name "Net-(U11-IO17)") (class "Default")
      (node (ref "PIN-OUT") (pin "13") (pinfunction "13_13") (pintype "passive"))
      (node (ref "U11") (pin "28") (pinfunction "IO17_28") (pintype "bidirectional"))
    )
    (net (code "189") (name "Net-(U11-IO18)") (class "Default")
      (node (ref "PIN-OUT") (pin "12") (pinfunction "12_12") (pintype "passive"))
      (node (ref "U11") (pin "30") (pinfunction "IO18_30") (pintype "bidirectional"))
    )
    (net (code "190") (name "Net-(U11-IO19)") (class "Default")
      (node (ref "PIN-OUT") (pin "11") (pinfunction "11_11") (pintype "passive"))
      (node (ref "U11") (pin "31") (pinfunction "IO19_31") (pintype "bidirectional"))
    )
    (net (code "191") (name "Net-(U11-IO21)") (class "Default")
      (node (ref "PIN-OUT") (pin "10") (pinfunction "10_10") (pintype "passive"))
      (node (ref "U11") (pin "33") (pinfunction "IO21_33") (pintype "bidirectional"))
    )
    (net (code "192") (name "Net-(U11-IO22)") (class "Default")
      (node (ref "PIN-OUT") (pin "9") (pinfunction "9_9") (pintype "passive"))
      (node (ref "U11") (pin "36") (pinfunction "IO22_36") (pintype "bidirectional"))
    )
    (net (code "193") (name "Net-(U11-IO23)") (class "Default")
      (node (ref "PIN-OUT") (pin "8") (pinfunction "8_8") (pintype "passive"))
      (node (ref "U11") (pin "37") (pinfunction "IO23_37") (pintype "bidirectional"))
    )
    (net (code "194") (name "Net-(U11-IO25)") (class "Default")
      (node (ref "PIN-OUT") (pin "7") (pinfunction "7_7") (pintype "passive"))
      (node (ref "U11") (pin "10") (pinfunction "IO25_10") (pintype "bidirectional"))
    )
    (net (code "195") (name "Net-(U11-IO26)") (class "Default")
      (node (ref "PIN-OUT") (pin "6") (pinfunction "6_6") (pintype "passive"))
      (node (ref "U11") (pin "11") (pinfunction "IO26_11") (pintype "bidirectional"))
    )
    (net (code "196") (name "Net-(U11-IO27)") (class "Default")
      (node (ref "PIN-OUT") (pin "5") (pinfunction "5_5") (pintype "passive"))
      (node (ref "U11") (pin "12") (pinfunction "IO27_12") (pintype "bidirectional"))
    )
    (net (code "197") (name "Net-(U11-IO32)") (class "Default")
      (node (ref "PIN-OUT") (pin "4") (pinfunction "4_4") (pintype "passive"))
      (node (ref "U11") (pin "8") (pinfunction "IO32_8") (pintype "bidirectional"))
    )
    (net (code "198") (name "Net-(U11-IO33)") (class "Default")
      (node (ref "PIN-OUT") (pin "3") (pinfunction "3_3") (pintype "passive"))
      (node (ref "U11") (pin "9") (pinfunction "IO33_9") (pintype "bidirectional"))
    )
    (net (code "199") (name "Net-(U11-IO34)") (class "Default")
      (node (ref "PIN-OUT") (pin "2") (pinfunction "2_2") (pintype "passive"))
      (node (ref "U11") (pin "6") (pinfunction "IO34_6") (pintype "bidirectional"))
    )
    (net (code "200") (name "Net-(U11-IO35)") (class "Default")
      (node (ref "PIN-OUT") (pin "1") (pinfunction "1_1") (pintype "passive"))
      (node (ref "U11") (pin "7") (pinfunction "IO35_7") (pintype "bidirectional"))
    )
    (net (code "201") (name "Net-(U11-NC)") (class "Default")
      (node (ref "P23") (pin "6") (pinfunction "6_6") (pintype "passive"))
      (node (ref "U11") (pin "32") (pinfunction "NC_32") (pintype "passive"))
    )
    (net (code "202") (name "Net-(U11-SENSOR_VN)") (class "Default")
      (node (ref "P23") (pin "5") (pinfunction "5_5") (pintype "passive"))
      (node (ref "U11") (pin "5") (pinfunction "SENSOR_VN_5") (pintype "input"))
    )
    (net (code "203") (name "Net-(U11-SENSOR_VP)") (class "Default")
      (node (ref "P23") (pin "4") (pinfunction "4_4") (pintype "passive"))
      (node (ref "U11") (pin "4") (pinfunction "SENSOR_VP_4") (pintype "input"))
    )
    (net (code "204") (name "Net-(U12-AD0{slash}DIO0)") (class "Default")
      (node (ref "P2") (pin "7") (pinfunction "7_7") (pintype "passive"))
      (node (ref "U12") (pin "33") (pinfunction "AD0/DIO0_33") (pintype "bidirectional"))
    )
    (net (code "205") (name "Net-(U12-AD1{slash}DIO1)") (class "Default")
      (node (ref "P2") (pin "6") (pinfunction "6_6") (pintype "passive"))
      (node (ref "U12") (pin "32") (pinfunction "AD1/DIO1_32") (pintype "bidirectional"))
    )
    (net (code "206") (name "Net-(U12-AD2{slash}DIO2)") (class "Default")
      (node (ref "P2") (pin "5") (pinfunction "5_5") (pintype "passive"))
      (node (ref "U12") (pin "31") (pinfunction "AD2/DIO2_31") (pintype "bidirectional"))
    )
    (net (code "207") (name "Net-(U12-AD3{slash}DIO3)") (class "Default")
      (node (ref "P2") (pin "4") (pinfunction "4_4") (pintype "passive"))
      (node (ref "U12") (pin "30") (pinfunction "AD3/DIO3_30") (pintype "bidirectional"))
    )
    (net (code "208") (name "Net-(U12-DIO4)") (class "Default")
      (node (ref "P2") (pin "2") (pinfunction "2_2") (pintype "passive"))
      (node (ref "U12") (pin "24") (pinfunction "DIO4_24") (pintype "bidirectional"))
    )
    (net (code "209") (name "Net-(U12-DIO12)") (class "Default")
      (node (ref "P2") (pin "1") (pinfunction "1_1") (pintype "passive"))
      (node (ref "U12") (pin "5") (pinfunction "DIO12_5") (pintype "bidirectional"))
    )
    (net (code "210") (name "Net-(U15A-SW)") (class "Default")
      (node (ref "SW3") (pin "2") (pinfunction "2_2") (pintype "passive"))
      (node (ref "U15") (pin "18") (pinfunction "SW_18") (pintype "input"))
    )
    (net (code "211") (name "Net-(U15B-VCC)") (class "Default")
      (node (ref "C-VCC") (pin "2") (pinfunction "2_2") (pintype "passive"))
      (node (ref "C-VCCREG") (pin "2") (pinfunction "2_2") (pintype "passive"))
      (node (ref "U15") (pin "58") (pinfunction "VCC_58") (pintype "power_in"))
      (node (ref "U15") (pin "60") (pinfunction "VCCREG_60") (pintype "power_in"))
    )
    (net (code "212") (name "Net-(U15B-VDDIO)") (class "Default")
      (node (ref "C-VDD") (pin "2") (pinfunction "2_2") (pintype "passive"))
      (node (ref "C-VREG") (pin "2") (pinfunction "2_2") (pintype "passive"))
      (node (ref "C-VREGPOL") (pin "1") (pinfunction "1_1") (pintype "passive"))
      (node (ref "R20") (pin "2") (pinfunction "2_2") (pintype "passive"))
      (node (ref "R21") (pin "2") (pinfunction "2_2") (pintype "passive"))
      (node (ref "U15") (pin "13") (pinfunction "VDDIO_13") (pintype "power_in"))
      (node (ref "U15") (pin "62") (pinfunction "VREG_62") (pintype "power_in"))
    )
    (net (code "213") (name "VCC") (class "Default")
      (node (ref "C14") (pin "2") (pinfunction "2_2") (pintype "passive"))
      (node (ref "IC4") (pin "32") (pinfunction "AVCC_32") (pintype "power_in"))
      (node (ref "IC4") (pin "4") (pinfunction "VCC_4") (pintype "power_in"))
    )
    (net (code "214") (name "unconnected-(CP2104-GPIO.0-Pad14)") (class "Default")
      (node (ref "CP2104") (pin "14") (pinfunction "GPIO.0_14") (pintype "bidirectional"))
    )
    (net (code "215") (name "unconnected-(CP2104-GPIO.1-Pad13)") (class "Default")
      (node (ref "CP2104") (pin "13") (pinfunction "GPIO.1_13") (pintype "bidirectional"))
    )
    (net (code "216") (name "unconnected-(CP2104-GPIO.2-Pad12)") (class "Default")
      (node (ref "CP2104") (pin "12") (pinfunction "GPIO.2_12") (pintype "bidirectional"))
    )
    (net (code "217") (name "unconnected-(CP2104-GPIO.3-Pad11)") (class "Default")
      (node (ref "CP2104") (pin "11") (pinfunction "GPIO.3_11") (pintype "bidirectional"))
    )
    (net (code "218") (name "unconnected-(CP2104-NC-Pad10)") (class "Default")
      (node (ref "CP2104") (pin "10") (pinfunction "NC_10") (pintype "passive+no_connect"))
    )
    (net (code "219") (name "unconnected-(CP2104-SUSPEND-Pad17)") (class "Default")
      (node (ref "CP2104") (pin "17") (pinfunction "SUSPEND_17") (pintype "output"))
    )
    (net (code "220") (name "unconnected-(CP2104-~{CTS}-Pad18)") (class "Default")
      (node (ref "CP2104") (pin "18") (pinfunction "~{CTS}_18") (pintype "input"))
    )
    (net (code "221") (name "unconnected-(CP2104-~{DCD}-Pad24)") (class "Default")
      (node (ref "CP2104") (pin "24") (pinfunction "~{DCD}_24") (pintype "input"))
    )
    (net (code "222") (name "unconnected-(CP2104-~{DSR}-Pad22)") (class "Default")
      (node (ref "CP2104") (pin "22") (pinfunction "~{DSR}_22") (pintype "input"))
    )
    (net (code "223") (name "unconnected-(CP2104-~{RI}-Pad1)") (class "Default")
      (node (ref "CP2104") (pin "1") (pinfunction "~{RI}_1") (pintype "input"))
    )
    (net (code "224") (name "unconnected-(CP2104-~{SUSPEND}-Pad15)") (class "Default")
      (node (ref "CP2104") (pin "15") (pinfunction "~{SUSPEND}_15") (pintype "output"))
    )
    (net (code "225") (name "unconnected-(Camera-Pad6)") (class "Default")
      (node (ref "Camera") (pin "6") (pinfunction "6_6") (pintype "passive"))
    )
    (net (code "226") (name "unconnected-(IC3-BYPASS-Pad4)") (class "Default")
      (node (ref "IC3") (pin "4") (pinfunction "BYPASS_4") (pintype "passive"))
    )
    (net (code "227") (name "unconnected-(IC4-PB0_(~{SS}{slash}PCINT0)-Pad14)") (class "Default")
      (node (ref "IC4") (pin "14") (pinfunction "PB0_(~{SS}/PCINT0)_14") (pintype "bidirectional"))
    )
    (net (code "228") (name "unconnected-(IC4-PB4_(T1{slash}PCINT4)-Pad18)") (class "Default")
      (node (ref "IC4") (pin "18") (pinfunction "PB4_(T1/PCINT4)_18") (pintype "bidirectional"))
    )
    (net (code "229") (name "unconnected-(IC4-PB5_(PCINT5)-Pad19)") (class "Default")
      (node (ref "IC4") (pin "19") (pinfunction "PB5_(PCINT5)_19") (pintype "bidirectional"))
    )
    (net (code "230") (name "unconnected-(IC4-PB6_(PCINT6)-Pad20)") (class "Default")
      (node (ref "IC4") (pin "20") (pinfunction "PB6_(PCINT6)_20") (pintype "bidirectional"))
    )
    (net (code "231") (name "unconnected-(IC4-PB7_(PCINT7{slash}OC.0A{slash}OC.1C)-Pad21)") (class "Default")
      (node (ref "IC4") (pin "21") (pinfunction "PB7_(PCINT7/OC.0A/OC.1C)_21") (pintype "bidirectional"))
    )
    (net (code "232") (name "unconnected-(IC4-PC2_(PCINT11{slash}AIN2)-Pad5)") (class "Default")
      (node (ref "IC4") (pin "5") (pinfunction "PC2_(PCINT11/AIN2)_5") (pintype "bidirectional"))
    )
    (net (code "233") (name "unconnected-(IC4-PC4_(PCINT10)-Pad26)") (class "Default")
      (node (ref "IC4") (pin "26") (pinfunction "PC4_(PCINT10)_26") (pintype "bidirectional"))
    )
    (net (code "234") (name "unconnected-(IC4-PC5_(PCINT9{slash}OC.1B)-Pad25)") (class "Default")
      (node (ref "IC4") (pin "25") (pinfunction "PC5_(PCINT9/OC.1B)_25") (pintype "bidirectional"))
    )
    (net (code "235") (name "unconnected-(IC4-PC6_(OC.1A{slash}PCINT8)-Pad23)") (class "Default")
      (node (ref "IC4") (pin "23") (pinfunction "PC6_(OC.1A/PCINT8)_23") (pintype "bidirectional"))
    )
    (net (code "236") (name "unconnected-(IC4-PC7_(INT4{slash}ICP1{slash}CLKO)-Pad22)") (class "Default")
      (node (ref "IC4") (pin "22") (pinfunction "PC7_(INT4/ICP1/CLKO)_22") (pintype "bidirectional"))
    )
    (net (code "237") (name "unconnected-(IC4-PD0_(OC.0B{slash}INT0)-Pad6)") (class "Default")
      (node (ref "IC4") (pin "6") (pinfunction "PD0_(OC.0B/INT0)_6") (pintype "bidirectional"))
    )
    (net (code "238") (name "unconnected-(IC4-PD1_(AIN0{slash}INT1)-Pad7)") (class "Default")
      (node (ref "IC4") (pin "7") (pinfunction "PD1_(AIN0/INT1)_7") (pintype "bidirectional"))
    )
    (net (code "239") (name "unconnected-(IC4-PD6_(~{RTS}{slash}AIN5{slash}INT6)-Pad12)") (class "Default")
      (node (ref "IC4") (pin "12") (pinfunction "PD6_(~{RTS}/AIN5/INT6)_12") (pintype "bidirectional"))
    )
    (net (code "240") (name "unconnected-(J1-ID-Pad4)") (class "Default")
      (node (ref "J1") (pin "4") (pinfunction "ID_4") (pintype "passive"))
    )
    (net (code "241") (name "unconnected-(J2-CC1-PadA5)") (class "Default")
      (node (ref "J2") (pin "A5") (pinfunction "CC1_A5") (pintype "passive"))
    )
    (net (code "242") (name "unconnected-(J2-CC2-PadB5)") (class "Default")
      (node (ref "J2") (pin "B5") (pinfunction "CC2_B5") (pintype "passive"))
    )
    (net (code "243") (name "unconnected-(J2-SBU1-PadA8)") (class "Default")
      (node (ref "J2") (pin "A8") (pinfunction "SBU1_A8") (pintype "passive"))
    )
    (net (code "244") (name "unconnected-(J2-SBU2-PadB8)") (class "Default")
      (node (ref "J2") (pin "B8") (pinfunction "SBU2_B8") (pintype "passive"))
    )
    (net (code "245") (name "unconnected-(J2-SSRXn1-PadB10)") (class "Default")
      (node (ref "J2") (pin "B10") (pinfunction "SSRXn1_B10") (pintype "passive"))
    )
    (net (code "246") (name "unconnected-(J2-SSRXn2-PadA10)") (class "Default")
      (node (ref "J2") (pin "A10") (pinfunction "SSRXn2_A10") (pintype "passive"))
    )
    (net (code "247") (name "unconnected-(J2-SSRXp1-PadB11)") (class "Default")
      (node (ref "J2") (pin "B11") (pinfunction "SSRXp1_B11") (pintype "passive"))
    )
    (net (code "248") (name "unconnected-(J2-SSRXp2-PadA11)") (class "Default")
      (node (ref "J2") (pin "A11") (pinfunction "SSRXp2_A11") (pintype "passive"))
    )
    (net (code "249") (name "unconnected-(J2-SSTXn1-PadA3)") (class "Default")
      (node (ref "J2") (pin "A3") (pinfunction "SSTXn1_A3") (pintype "passive"))
    )
    (net (code "250") (name "unconnected-(J2-SSTXn2-PadB3)") (class "Default")
      (node (ref "J2") (pin "B3") (pinfunction "SSTXn2_B3") (pintype "passive"))
    )
    (net (code "251") (name "unconnected-(J2-SSTXp1-PadA2)") (class "Default")
      (node (ref "J2") (pin "A2") (pinfunction "SSTXp1_A2") (pintype "passive"))
    )
    (net (code "252") (name "unconnected-(J2-SSTXp2-PadB2)") (class "Default")
      (node (ref "J2") (pin "B2") (pinfunction "SSTXp2_B2") (pintype "passive"))
    )
    (net (code "253") (name "unconnected-(J3-ID-Pad4)") (class "Default")
      (node (ref "J3") (pin "4") (pinfunction "ID_4") (pintype "passive"))
    )
    (net (code "254") (name "unconnected-(J4-CC1-PadA5)") (class "Default")
      (node (ref "J4") (pin "A5") (pinfunction "CC1_A5") (pintype "passive"))
    )
    (net (code "255") (name "unconnected-(J4-CC2-PadB5)") (class "Default")
      (node (ref "J4") (pin "B5") (pinfunction "CC2_B5") (pintype "passive"))
    )
    (net (code "256") (name "unconnected-(J4-SBU1-PadA8)") (class "Default")
      (node (ref "J4") (pin "A8") (pinfunction "SBU1_A8") (pintype "passive"))
    )
    (net (code "257") (name "unconnected-(J4-SBU2-PadB8)") (class "Default")
      (node (ref "J4") (pin "B8") (pinfunction "SBU2_B8") (pintype "passive"))
    )
    (net (code "258") (name "unconnected-(J4-SSRXn1-PadB10)") (class "Default")
      (node (ref "J4") (pin "B10") (pinfunction "SSRXn1_B10") (pintype "passive"))
    )
    (net (code "259") (name "unconnected-(J4-SSRXn2-PadA10)") (class "Default")
      (node (ref "J4") (pin "A10") (pinfunction "SSRXn2_A10") (pintype "passive"))
    )
    (net (code "260") (name "unconnected-(J4-SSRXp1-PadB11)") (class "Default")
      (node (ref "J4") (pin "B11") (pinfunction "SSRXp1_B11") (pintype "passive"))
    )
    (net (code "261") (name "unconnected-(J4-SSRXp2-PadA11)") (class "Default")
      (node (ref "J4") (pin "A11") (pinfunction "SSRXp2_A11") (pintype "passive"))
    )
    (net (code "262") (name "unconnected-(J4-SSTXn1-PadA3)") (class "Default")
      (node (ref "J4") (pin "A3") (pinfunction "SSTXn1_A3") (pintype "passive"))
    )
    (net (code "263") (name "unconnected-(J4-SSTXn2-PadB3)") (class "Default")
      (node (ref "J4") (pin "B3") (pinfunction "SSTXn2_B3") (pintype "passive"))
    )
    (net (code "264") (name "unconnected-(J4-SSTXp1-PadA2)") (class "Default")
      (node (ref "J4") (pin "A2") (pinfunction "SSTXp1_A2") (pintype "passive"))
    )
    (net (code "265") (name "unconnected-(J4-SSTXp2-PadB2)") (class "Default")
      (node (ref "J4") (pin "B2") (pinfunction "SSTXp2_B2") (pintype "passive"))
    )
    (net (code "266") (name "unconnected-(P2-Pad3)") (class "Default")
      (node (ref "P2") (pin "3") (pinfunction "3_3") (pintype "passive"))
    )
    (net (code "267") (name "unconnected-(P5-Pad1)") (class "Default")
      (node (ref "P5") (pin "1") (pinfunction "1_1") (pintype "passive"))
    )
    (net (code "268") (name "unconnected-(P5-Pad2)") (class "Default")
      (node (ref "P5") (pin "2") (pinfunction "2_2") (pintype "passive"))
    )
    (net (code "269") (name "unconnected-(P5-Pad3)") (class "Default")
      (node (ref "P5") (pin "3") (pinfunction "3_3") (pintype "passive"))
    )
    (net (code "270") (name "unconnected-(P5-Pad4)") (class "Default")
      (node (ref "P5") (pin "4") (pinfunction "4_4") (pintype "passive"))
    )
    (net (code "271") (name "unconnected-(P5-Pad5)") (class "Default")
      (node (ref "P5") (pin "5") (pinfunction "5_5") (pintype "passive"))
    )
    (net (code "272") (name "unconnected-(P5-Pad6)") (class "Default")
      (node (ref "P5") (pin "6") (pinfunction "6_6") (pintype "passive"))
    )
    (net (code "273") (name "unconnected-(P5-PadMP1)") (class "Default")
      (node (ref "P5") (pin "MP1") (pinfunction "MP1_MP1") (pintype "passive"))
    )
    (net (code "274") (name "unconnected-(P5-PadMP2)") (class "Default")
      (node (ref "P5") (pin "MP2") (pinfunction "MP2_MP2") (pintype "passive"))
    )
    (net (code "275") (name "unconnected-(P8-PadMP1)") (class "Default")
      (node (ref "P8") (pin "MP1") (pinfunction "MP1_MP1") (pintype "passive"))
    )
    (net (code "276") (name "unconnected-(P8-PadMP2)") (class "Default")
      (node (ref "P8") (pin "MP2") (pinfunction "MP2_MP2") (pintype "passive"))
    )
    (net (code "277") (name "unconnected-(P9-PadMP1)") (class "Default")
      (node (ref "P9") (pin "MP1") (pinfunction "MP1_MP1") (pintype "passive"))
    )
    (net (code "278") (name "unconnected-(P9-PadMP2)") (class "Default")
      (node (ref "P9") (pin "MP2") (pinfunction "MP2_MP2") (pintype "passive"))
    )
    (net (code "279") (name "unconnected-(P10-PadMP1)") (class "Default")
      (node (ref "P10") (pin "MP1") (pinfunction "MP1_MP1") (pintype "passive"))
    )
    (net (code "280") (name "unconnected-(P10-PadMP2)") (class "Default")
      (node (ref "P10") (pin "MP2") (pinfunction "MP2_MP2") (pintype "passive"))
    )
    (net (code "281") (name "unconnected-(P11-PadMP1)") (class "Default")
      (node (ref "P11") (pin "MP1") (pinfunction "MP1_MP1") (pintype "passive"))
    )
    (net (code "282") (name "unconnected-(P11-PadMP2)") (class "Default")
      (node (ref "P11") (pin "MP2") (pinfunction "MP2_MP2") (pintype "passive"))
    )
    (net (code "283") (name "unconnected-(P15-Pad9)") (class "Default")
      (node (ref "P15") (pin "9") (pinfunction "9_9") (pintype "passive"))
    )
    (net (code "284") (name "unconnected-(P18-Pad9)") (class "Default")
      (node (ref "P18") (pin "9") (pinfunction "9_9") (pintype "passive"))
    )
    (net (code "285") (name "unconnected-(TEST-HEADER1-Pad1)") (class "Default")
      (node (ref "TEST-HEADER1") (pin "1") (pinfunction "1_1") (pintype "passive"))
    )
    (net (code "286") (name "unconnected-(U1A-V+-Pad8)") (class "Default")
      (node (ref "U1") (pin "8") (pinfunction "V+_8") (pintype "power_in"))
    )
    (net (code "287") (name "unconnected-(U1A-V--Pad4)") (class "Default")
      (node (ref "U1") (pin "4") (pinfunction "V-_4") (pintype "power_in"))
    )
    (net (code "288") (name "unconnected-(U10-DOUT-Pad2)") (class "Default")
      (node (ref "U10") (pin "2") (pinfunction "DOUT_2") (pintype "output"))
    )
    (net (code "289") (name "unconnected-(U12-ASSOCIATE{slash}DIO5-Pad28)") (class "Default")
      (node (ref "U12") (pin "28") (pinfunction "ASSOCIATE/DIO5_28") (pintype "bidirectional"))
    )
    (net (code "290") (name "unconnected-(U12-ON{slash}~{SLEEP}{slash}DIO9-Pad26)") (class "Default")
      (node (ref "U12") (pin "26") (pinfunction "ON/~{SLEEP}/DIO9_26") (pintype "bidirectional"))
    )
    (net (code "291") (name "unconnected-(U12-PWM1{slash}DIO11-Pad8)") (class "Default")
      (node (ref "U12") (pin "8") (pinfunction "PWM1/DIO11_8") (pintype "bidirectional"))
    )
    (net (code "292") (name "unconnected-(U12-RESERVED-Pad9)") (class "Default")
      (node (ref "U12") (pin "9") (pinfunction "RESERVED_9") (pintype "passive"))
    )
    (net (code "293") (name "unconnected-(U12-RESERVED-Pad18)") (class "Default")
      (node (ref "U12") (pin "18") (pinfunction "RESERVED_18") (pintype "passive"))
    )
    (net (code "294") (name "unconnected-(U12-RESERVED-Pad19)") (class "Default")
      (node (ref "U12") (pin "19") (pinfunction "RESERVED_19") (pintype "passive"))
    )
    (net (code "295") (name "unconnected-(U12-RESERVED-Pad20)") (class "Default")
      (node (ref "U12") (pin "20") (pinfunction "RESERVED_20") (pintype "passive"))
    )
    (net (code "296") (name "unconnected-(U12-RESERVED-Pad21)") (class "Default")
      (node (ref "U12") (pin "21") (pinfunction "RESERVED_21") (pintype "passive"))
    )
    (net (code "297") (name "unconnected-(U12-RESERVED-Pad23)") (class "Default")
      (node (ref "U12") (pin "23") (pinfunction "RESERVED_23") (pintype "passive"))
    )
    (net (code "298") (name "unconnected-(U12-RESERVED-Pad34)") (class "Default")
      (node (ref "U12") (pin "34") (pinfunction "RESERVED_34") (pintype "passive"))
    )
    (net (code "299") (name "unconnected-(U12-RESERVED-Pad37)") (class "Default")
      (node (ref "U12") (pin "37") (pinfunction "RESERVED_37") (pintype "passive"))
    )
    (net (code "300") (name "unconnected-(U12-RF-Pad36)") (class "Default")
      (node (ref "U12") (pin "36") (pinfunction "RF_36") (pintype "bidirectional"))
    )
    (net (code "301") (name "unconnected-(U12-RSSI_PWM{slash}DIO10-Pad7)") (class "Default")
      (node (ref "U12") (pin "7") (pinfunction "RSSI_PWM/DIO10_7") (pintype "bidirectional"))
    )
    (net (code "302") (name "unconnected-(U12-SPI_CLK{slash}DIO18-Pad14)") (class "Default")
      (node (ref "U12") (pin "14") (pinfunction "SPI_CLK/DIO18_14") (pintype "bidirectional"))
    )
    (net (code "303") (name "unconnected-(U12-SPI_MISO{slash}DIO15-Pad17)") (class "Default")
      (node (ref "U12") (pin "17") (pinfunction "SPI_MISO/DIO15_17") (pintype "bidirectional"))
    )
    (net (code "304") (name "unconnected-(U12-SPI_MOSI{slash}DIO16-Pad16)") (class "Default")
      (node (ref "U12") (pin "16") (pinfunction "SPI_MOSI/DIO16_16") (pintype "bidirectional"))
    )
    (net (code "305") (name "unconnected-(U12-SPI_~{ATTN}{slash}~{BOOTMODE}{slash}DIO19-Pad12)") (class "Default")
      (node (ref "U12") (pin "12") (pinfunction "SPI_~{ATTN}/~{BOOTMODE}/DIO19_12") (pintype "bidirectional"))
    )
    (net (code "306") (name "unconnected-(U12-SPI_~{SSEL}{slash}DIO17-Pad15)") (class "Default")
      (node (ref "U12") (pin "15") (pinfunction "SPI_~{SSEL}/DIO17_15") (pintype "bidirectional"))
    )
    (net (code "307") (name "unconnected-(U12-VREF-Pad27)") (class "Default")
      (node (ref "U12") (pin "27") (pinfunction "VREF_27") (pintype "input"))
    )
    (net (code "308") (name "unconnected-(U12-~{CTS}{slash}DIO7-Pad25)") (class "Default")
      (node (ref "U12") (pin "25") (pinfunction "~{CTS}/DIO7_25") (pintype "bidirectional"))
    )
    (net (code "309") (name "unconnected-(U12-~{DTR}{slash}SLEEP_RQ{slash}DIO8-Pad10)") (class "Default")
      (node (ref "U12") (pin "10") (pinfunction "~{DTR}/SLEEP_RQ/DIO8_10") (pintype "bidirectional"))
    )
    (net (code "310") (name "unconnected-(U12-~{RESET}-Pad6)") (class "Default")
      (node (ref "U12") (pin "6") (pinfunction "~{RESET}_6") (pintype "input"))
    )
    (net (code "311") (name "unconnected-(U12-~{RTS}{slash}DIO6-Pad29)") (class "Default")
      (node (ref "U12") (pin "29") (pinfunction "~{RTS}/DIO6_29") (pintype "bidirectional"))
    )
    (net (code "312") (name "unconnected-(U15A-OSCIN-Pad63)") (class "Default")
      (node (ref "U15") (pin "63") (pinfunction "OSCIN_63") (pintype "input"))
    )
    (net (code "313") (name "unconnected-(U15A-OSCOUT-Pad64)") (class "Default")
      (node (ref "U15") (pin "64") (pinfunction "OSCOUT_64") (pintype "passive"))
    )
  )
)
